# reg-board.net
KiCad netlist of a schematic drawn in EAGLE
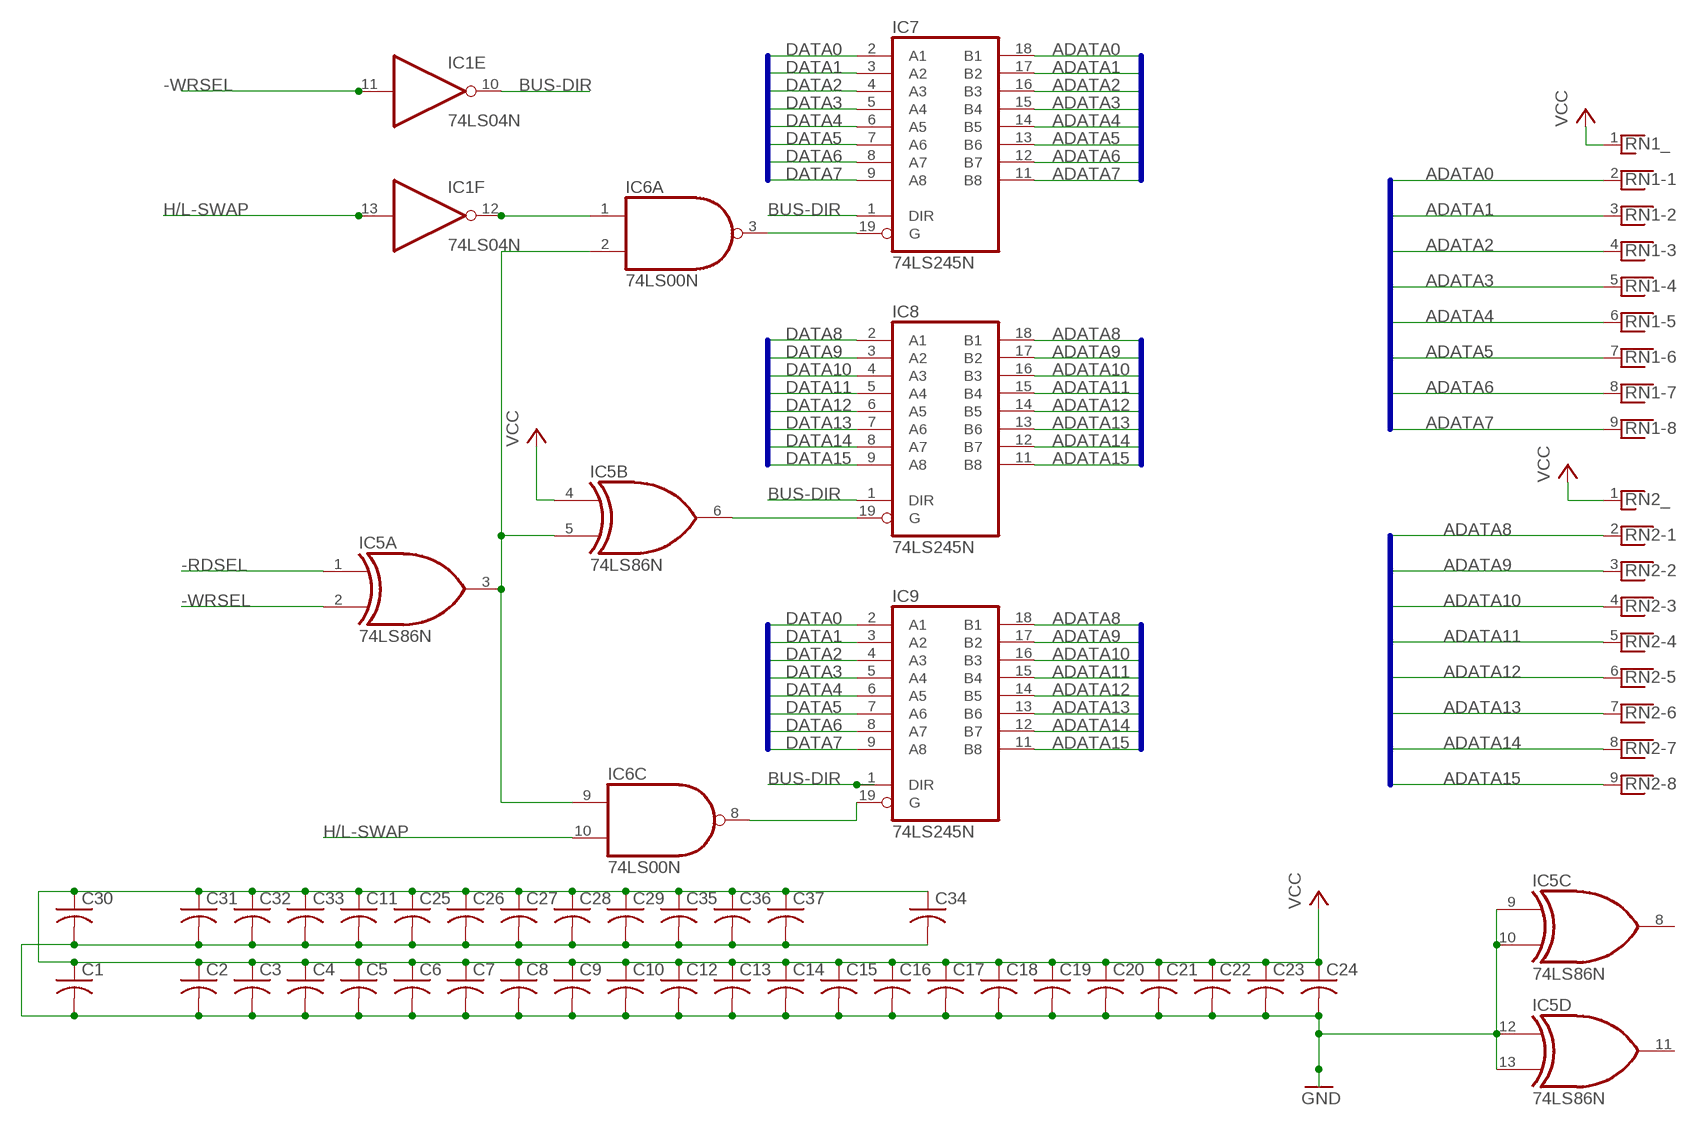
[diagram p0: schematic, sheet 1]
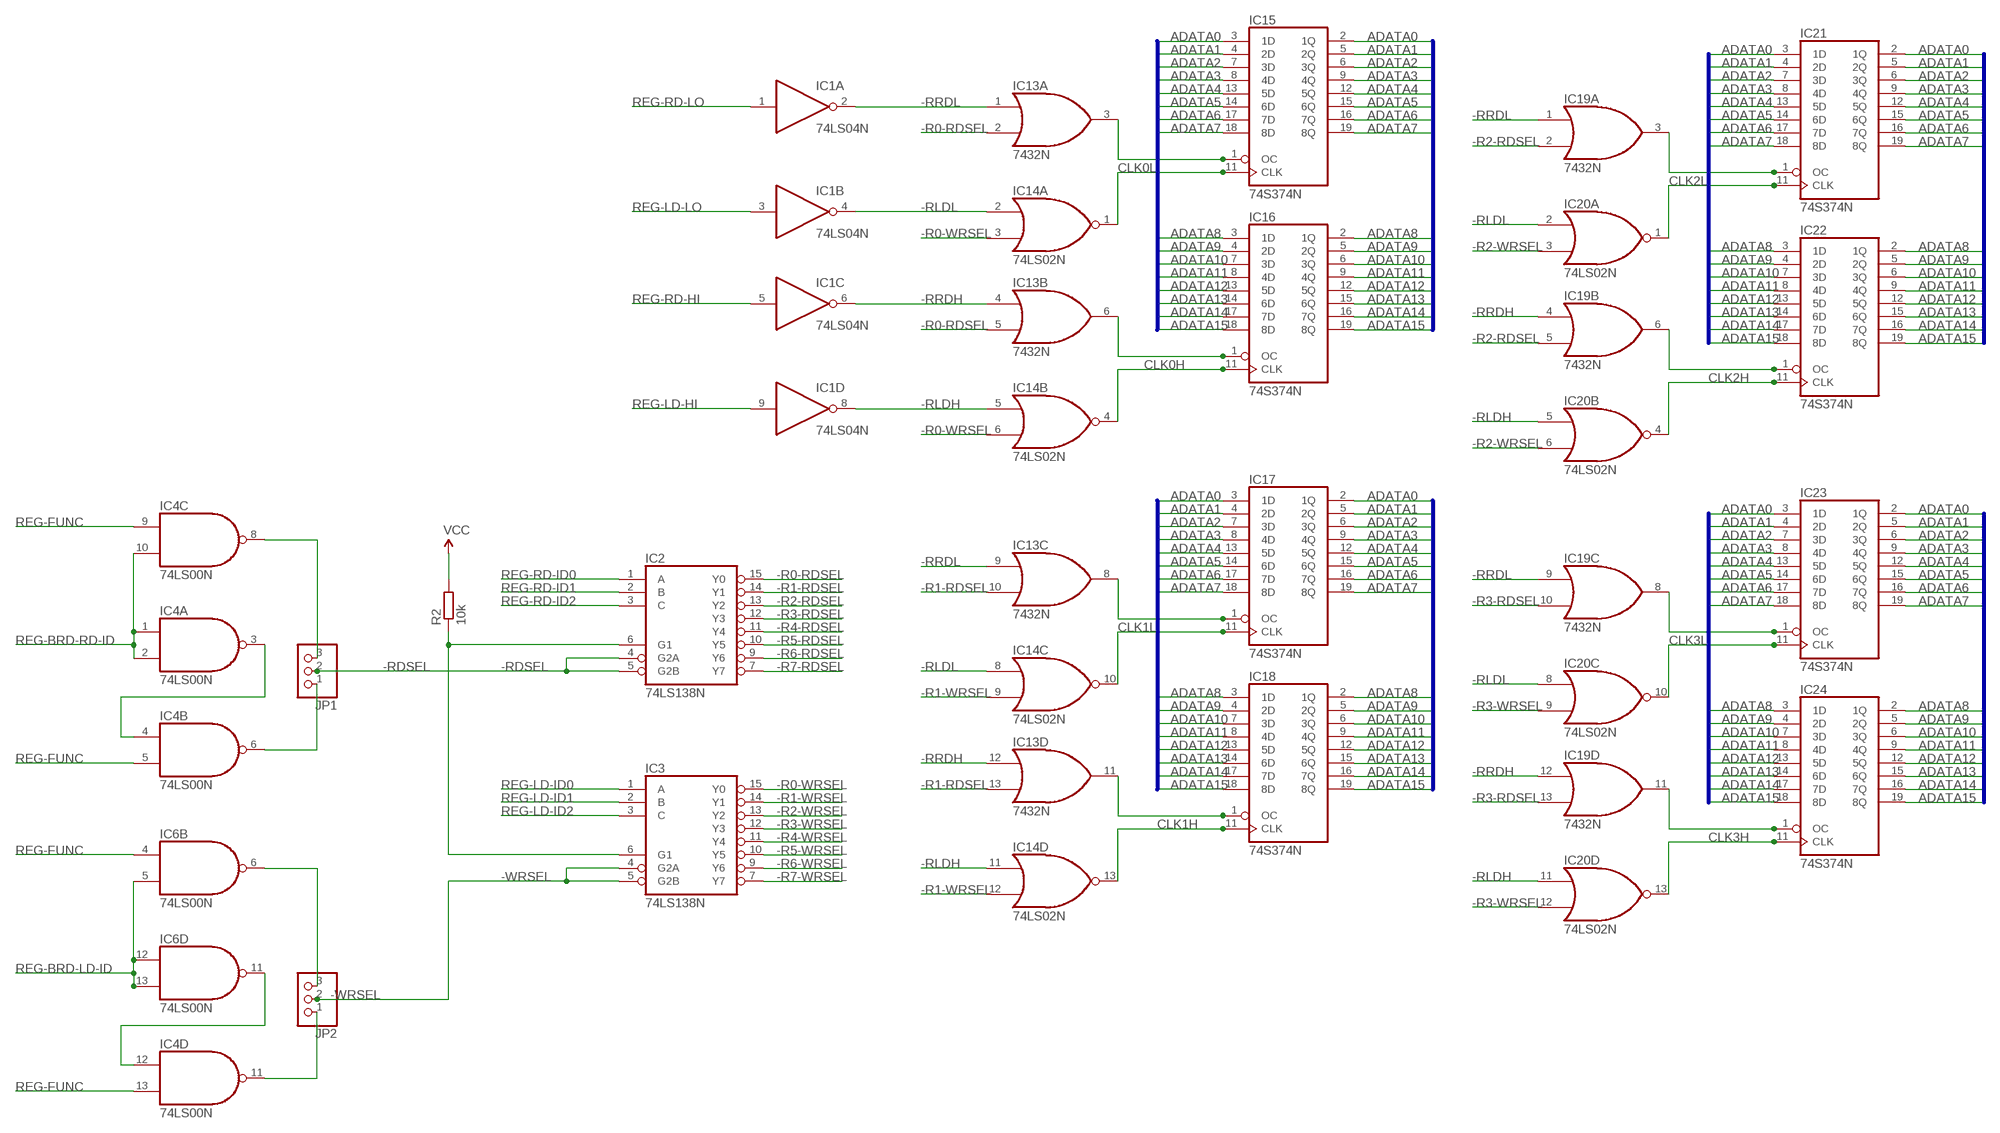
[diagram p1: schematic, sheet 2]
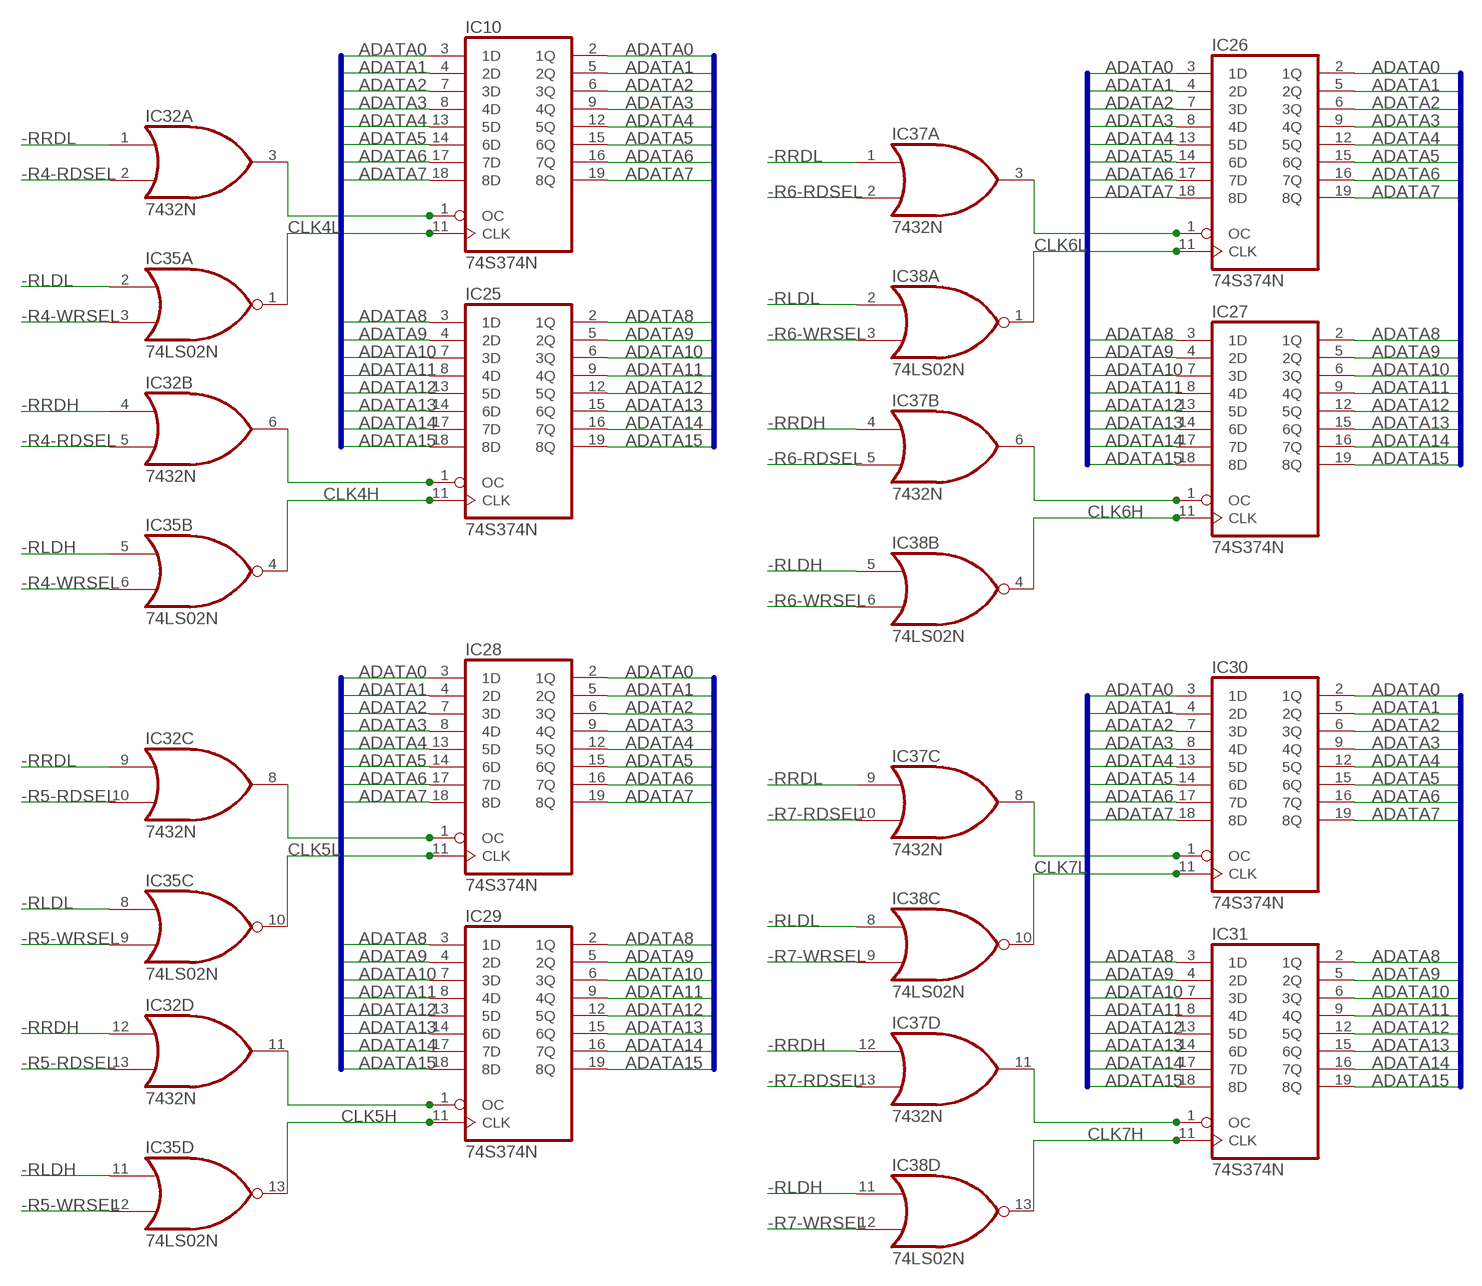
[diagram p2: schematic, sheet 3]
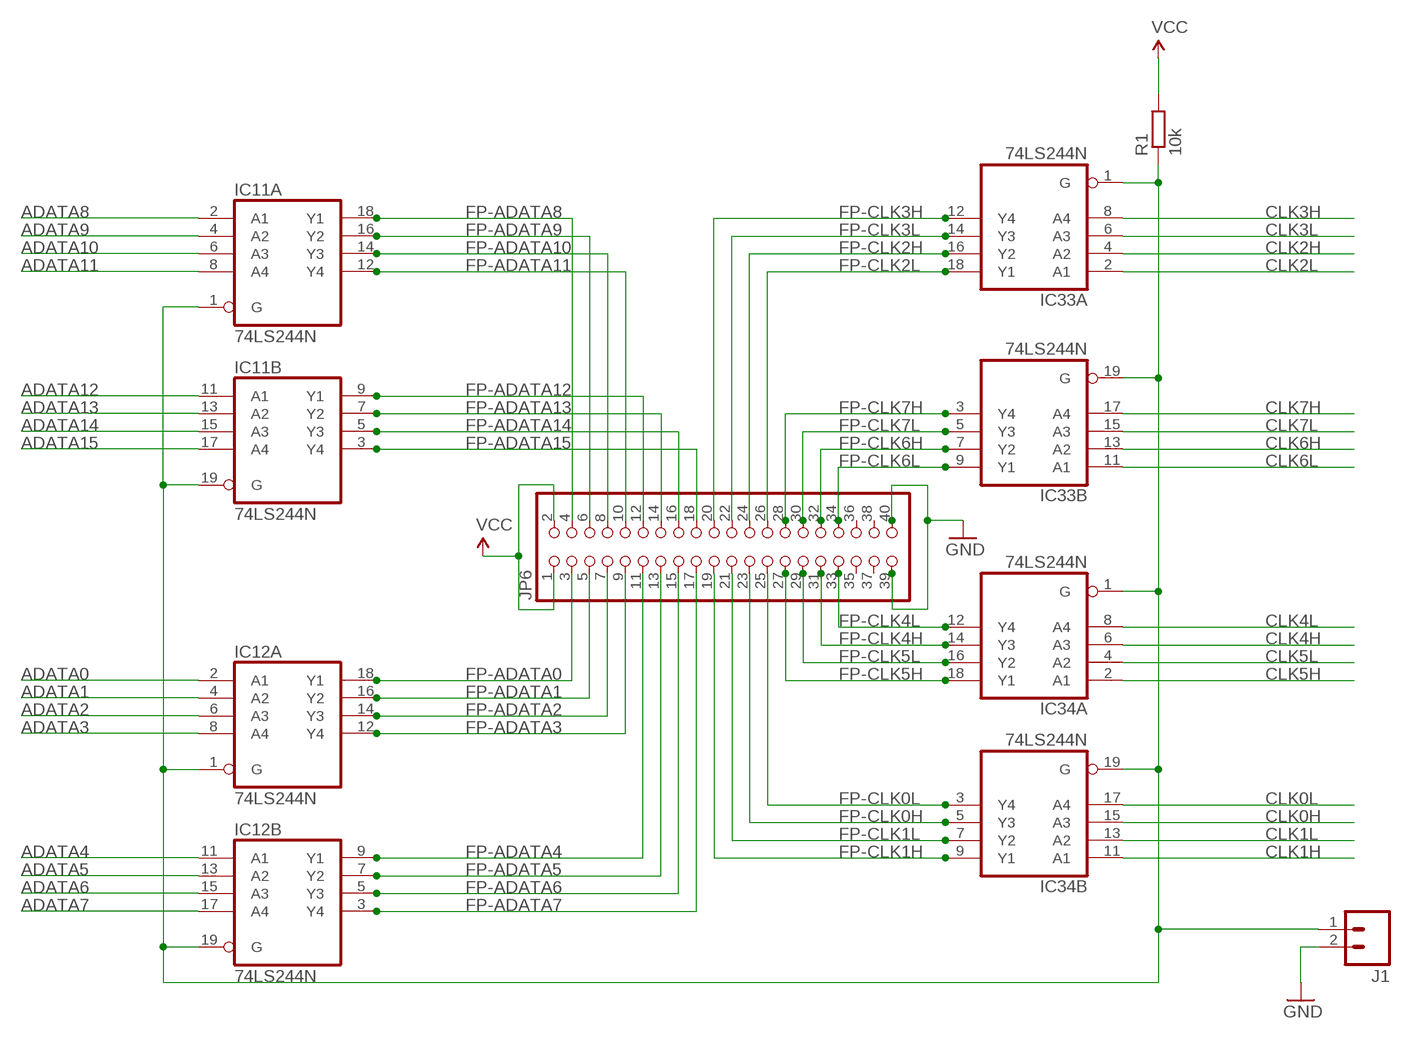
[diagram p3: schematic, sheet 4]
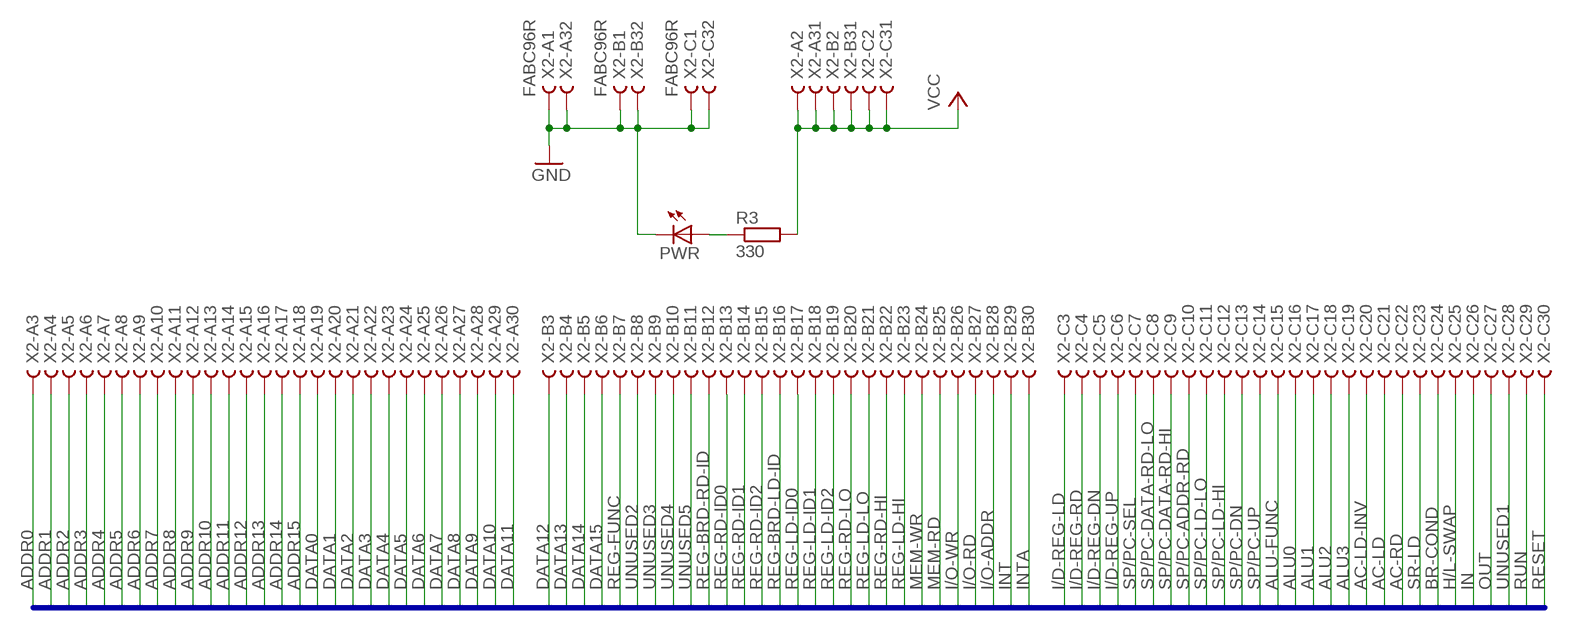
[diagram p4: schematic, sheet 5]

(export (version "E")
  (design (tool "Eeschema 10.0.6"))
  (components
    (comp (ref "IC10")
      (value "74S374N")
      (footprint "eagle-import:DIL20")
      (libsource (lib "eagle-import") (part "74374NS"))
    )
    (comp (ref "IC25")
      (value "74S374N")
      (footprint "eagle-import:DIL20")
      (libsource (lib "eagle-import") (part "74374NS"))
    )
    (comp (ref "IC26")
      (value "74S374N")
      (footprint "eagle-import:DIL20")
      (libsource (lib "eagle-import") (part "74374NS"))
    )
    (comp (ref "IC27")
      (value "74S374N")
      (footprint "eagle-import:DIL20")
      (libsource (lib "eagle-import") (part "74374NS"))
    )
    (comp (ref "IC28")
      (value "74S374N")
      (footprint "eagle-import:DIL20")
      (libsource (lib "eagle-import") (part "74374NS"))
    )
    (comp (ref "IC29")
      (value "74S374N")
      (footprint "eagle-import:DIL20")
      (libsource (lib "eagle-import") (part "74374NS"))
    )
    (comp (ref "IC30")
      (value "74S374N")
      (footprint "eagle-import:DIL20")
      (libsource (lib "eagle-import") (part "74374NS"))
    )
    (comp (ref "IC31")
      (value "74S374N")
      (footprint "eagle-import:DIL20")
      (libsource (lib "eagle-import") (part "74374NS"))
    )
    (comp (ref "IC32")
      (value "7432N")
      (footprint "eagle-import:DIL14")
      (libsource (lib "eagle-import") (part "7432N"))
    )
    (comp (ref "IC35")
      (value "74LS02N")
      (footprint "eagle-import:DIL14")
      (libsource (lib "eagle-import") (part "7402NLS"))
    )
    (comp (ref "IC37")
      (value "7432N")
      (footprint "eagle-import:DIL14")
      (libsource (lib "eagle-import") (part "7432N"))
    )
    (comp (ref "IC38")
      (value "74LS02N")
      (footprint "eagle-import:DIL14")
      (libsource (lib "eagle-import") (part "7402NLS"))
    )
    (comp (ref "IC11")
      (value "74LS244N")
      (footprint "eagle-import:DIL20")
      (libsource (lib "eagle-import") (part "74xx-us_74244NLS"))
    )
    (comp (ref "IC12")
      (value "74LS244N")
      (footprint "eagle-import:DIL20")
      (libsource (lib "eagle-import") (part "74xx-us_74244NLS"))
    )
    (comp (ref "IC33")
      (value "74LS244N")
      (footprint "eagle-import:DIL20")
      (libsource (lib "eagle-import") (part "74xx-us_74244NLS"))
    )
    (comp (ref "IC34")
      (value "74LS244N")
      (footprint "eagle-import:DIL20")
      (libsource (lib "eagle-import") (part "74xx-us_74244NLS"))
    )
    (comp (ref "J1")
      (value "M02PTH")
      (footprint "eagle-import:1X02")
      (libsource (lib "eagle-import") (part "M02PTH"))
    )
    (comp (ref "JP6")
      (value "PINHD-2X20")
      (footprint "eagle-import:2X20")
      (libsource (lib "eagle-import") (part "PINHD-2X20"))
    )
    (comp (ref "R1")
      (value "10k")
      (footprint "eagle-import:0207_10")
      (libsource (lib "eagle-import") (part "R0207/10"))
    )
    (comp (ref "IC1")
      (value "74LS04N")
      (footprint "eagle-import:DIL14")
      (libsource (lib "eagle-import") (part "7404NLS"))
    )
    (comp (ref "IC2")
      (value "74LS138N")
      (footprint "eagle-import:DIL16")
      (libsource (lib "eagle-import") (part "74138NLS"))
    )
    (comp (ref "IC3")
      (value "74LS138N")
      (footprint "eagle-import:DIL16")
      (libsource (lib "eagle-import") (part "74138NLS"))
    )
    (comp (ref "IC4")
      (value "74LS00N")
      (footprint "eagle-import:DIL14")
      (libsource (lib "eagle-import") (part "7400NLS"))
    )
    (comp (ref "IC6")
      (value "74LS00N")
      (footprint "eagle-import:DIL14")
      (libsource (lib "eagle-import") (part "7400NLS"))
    )
    (comp (ref "IC13")
      (value "7432N")
      (footprint "eagle-import:DIL14")
      (libsource (lib "eagle-import") (part "7432N"))
    )
    (comp (ref "IC14")
      (value "74LS02N")
      (footprint "eagle-import:DIL14")
      (libsource (lib "eagle-import") (part "7402NLS"))
    )
    (comp (ref "IC15")
      (value "74S374N")
      (footprint "eagle-import:DIL20")
      (libsource (lib "eagle-import") (part "74374NS"))
    )
    (comp (ref "IC16")
      (value "74S374N")
      (footprint "eagle-import:DIL20")
      (libsource (lib "eagle-import") (part "74374NS"))
    )
    (comp (ref "IC17")
      (value "74S374N")
      (footprint "eagle-import:DIL20")
      (libsource (lib "eagle-import") (part "74374NS"))
    )
    (comp (ref "IC18")
      (value "74S374N")
      (footprint "eagle-import:DIL20")
      (libsource (lib "eagle-import") (part "74374NS"))
    )
    (comp (ref "IC19")
      (value "7432N")
      (footprint "eagle-import:DIL14")
      (libsource (lib "eagle-import") (part "7432N"))
    )
    (comp (ref "IC20")
      (value "74LS02N")
      (footprint "eagle-import:DIL14")
      (libsource (lib "eagle-import") (part "7402NLS"))
    )
    (comp (ref "IC21")
      (value "74S374N")
      (footprint "eagle-import:DIL20")
      (libsource (lib "eagle-import") (part "74374NS"))
    )
    (comp (ref "IC22")
      (value "74S374N")
      (footprint "eagle-import:DIL20")
      (libsource (lib "eagle-import") (part "74374NS"))
    )
    (comp (ref "IC23")
      (value "74S374N")
      (footprint "eagle-import:DIL20")
      (libsource (lib "eagle-import") (part "74374NS"))
    )
    (comp (ref "IC24")
      (value "74S374N")
      (footprint "eagle-import:DIL20")
      (libsource (lib "eagle-import") (part "74374NS"))
    )
    (comp (ref "JP1")
      (value "PINHD-1X3")
      (footprint "eagle-import:1X03")
      (libsource (lib "eagle-import") (part "PINHD-1X3"))
    )
    (comp (ref "JP2")
      (value "PINHD-1X3")
      (footprint "eagle-import:1X03")
      (libsource (lib "eagle-import") (part "PINHD-1X3"))
    )
    (comp (ref "R2")
      (value "10k")
      (footprint "eagle-import:0207_10")
      (libsource (lib "eagle-import") (part "R0207/10"))
    )
    (comp (ref "C1")
      (value "C-US025-040X050")
      (footprint "eagle-import:C025-040X050")
      (libsource (lib "eagle-import") (part "C-US025-040X050"))
    )
    (comp (ref "C2")
      (value "C-US025-040X050")
      (footprint "eagle-import:C025-040X050")
      (libsource (lib "eagle-import") (part "C-US025-040X050"))
    )
    (comp (ref "C3")
      (value "C-US025-040X050")
      (footprint "eagle-import:C025-040X050")
      (libsource (lib "eagle-import") (part "C-US025-040X050"))
    )
    (comp (ref "C4")
      (value "C-US025-040X050")
      (footprint "eagle-import:C025-040X050")
      (libsource (lib "eagle-import") (part "C-US025-040X050"))
    )
    (comp (ref "C5")
      (value "C-US025-040X050")
      (footprint "eagle-import:C025-040X050")
      (libsource (lib "eagle-import") (part "C-US025-040X050"))
    )
    (comp (ref "C6")
      (value "C-US025-040X050")
      (footprint "eagle-import:C025-040X050")
      (libsource (lib "eagle-import") (part "C-US025-040X050"))
    )
    (comp (ref "C7")
      (value "C-US025-040X050")
      (footprint "eagle-import:C025-040X050")
      (libsource (lib "eagle-import") (part "C-US025-040X050"))
    )
    (comp (ref "C8")
      (value "C-US025-040X050")
      (footprint "eagle-import:C025-040X050")
      (libsource (lib "eagle-import") (part "C-US025-040X050"))
    )
    (comp (ref "C9")
      (value "C-US025-040X050")
      (footprint "eagle-import:C025-040X050")
      (libsource (lib "eagle-import") (part "C-US025-040X050"))
    )
    (comp (ref "C10")
      (value "C-US025-040X050")
      (footprint "eagle-import:C025-040X050")
      (libsource (lib "eagle-import") (part "C-US025-040X050"))
    )
    (comp (ref "C11")
      (value "C-US025-040X050")
      (footprint "eagle-import:C025-040X050")
      (libsource (lib "eagle-import") (part "C-US025-040X050"))
    )
    (comp (ref "C12")
      (value "C-US025-040X050")
      (footprint "eagle-import:C025-040X050")
      (libsource (lib "eagle-import") (part "C-US025-040X050"))
    )
    (comp (ref "C13")
      (value "C-US025-040X050")
      (footprint "eagle-import:C025-040X050")
      (libsource (lib "eagle-import") (part "C-US025-040X050"))
    )
    (comp (ref "C14")
      (value "C-US025-040X050")
      (footprint "eagle-import:C025-040X050")
      (libsource (lib "eagle-import") (part "C-US025-040X050"))
    )
    (comp (ref "C15")
      (value "C-US025-040X050")
      (footprint "eagle-import:C025-040X050")
      (libsource (lib "eagle-import") (part "C-US025-040X050"))
    )
    (comp (ref "C16")
      (value "C-US025-040X050")
      (footprint "eagle-import:C025-040X050")
      (libsource (lib "eagle-import") (part "C-US025-040X050"))
    )
    (comp (ref "C17")
      (value "C-US025-040X050")
      (footprint "eagle-import:C025-040X050")
      (libsource (lib "eagle-import") (part "C-US025-040X050"))
    )
    (comp (ref "C18")
      (value "C-US025-040X050")
      (footprint "eagle-import:C025-040X050")
      (libsource (lib "eagle-import") (part "C-US025-040X050"))
    )
    (comp (ref "C19")
      (value "C-US025-040X050")
      (footprint "eagle-import:C025-040X050")
      (libsource (lib "eagle-import") (part "C-US025-040X050"))
    )
    (comp (ref "C20")
      (value "C-US025-040X050")
      (footprint "eagle-import:C025-040X050")
      (libsource (lib "eagle-import") (part "C-US025-040X050"))
    )
    (comp (ref "C21")
      (value "C-US025-040X050")
      (footprint "eagle-import:C025-040X050")
      (libsource (lib "eagle-import") (part "C-US025-040X050"))
    )
    (comp (ref "C22")
      (value "C-US025-040X050")
      (footprint "eagle-import:C025-040X050")
      (libsource (lib "eagle-import") (part "C-US025-040X050"))
    )
    (comp (ref "C23")
      (value "C-US025-040X050")
      (footprint "eagle-import:C025-040X050")
      (libsource (lib "eagle-import") (part "C-US025-040X050"))
    )
    (comp (ref "C24")
      (value "C-US025-040X050")
      (footprint "eagle-import:C025-040X050")
      (libsource (lib "eagle-import") (part "C-US025-040X050"))
    )
    (comp (ref "C25")
      (value "C-US025-040X050")
      (footprint "eagle-import:C025-040X050")
      (libsource (lib "eagle-import") (part "C-US025-040X050"))
    )
    (comp (ref "C26")
      (value "C-US025-040X050")
      (footprint "eagle-import:C025-040X050")
      (libsource (lib "eagle-import") (part "C-US025-040X050"))
    )
    (comp (ref "C27")
      (value "C-US025-040X050")
      (footprint "eagle-import:C025-040X050")
      (libsource (lib "eagle-import") (part "C-US025-040X050"))
    )
    (comp (ref "C28")
      (value "C-US025-040X050")
      (footprint "eagle-import:C025-040X050")
      (libsource (lib "eagle-import") (part "C-US025-040X050"))
    )
    (comp (ref "C29")
      (value "C-US025-040X050")
      (footprint "eagle-import:C025-040X050")
      (libsource (lib "eagle-import") (part "C-US025-040X050"))
    )
    (comp (ref "C30")
      (value "C-US025-040X050")
      (footprint "eagle-import:C025-040X050")
      (libsource (lib "eagle-import") (part "C-US025-040X050"))
    )
    (comp (ref "C31")
      (value "C-US025-040X050")
      (footprint "eagle-import:C025-040X050")
      (libsource (lib "eagle-import") (part "C-US025-040X050"))
    )
    (comp (ref "C32")
      (value "C-US025-040X050")
      (footprint "eagle-import:C025-040X050")
      (libsource (lib "eagle-import") (part "C-US025-040X050"))
    )
    (comp (ref "C33")
      (value "C-US025-040X050")
      (footprint "eagle-import:C025-040X050")
      (libsource (lib "eagle-import") (part "C-US025-040X050"))
    )
    (comp (ref "C34")
      (value "C-US025-040X050")
      (footprint "eagle-import:C025-040X050")
      (libsource (lib "eagle-import") (part "C-US025-040X050"))
    )
    (comp (ref "C35")
      (value "C-US025-040X050")
      (footprint "eagle-import:C025-040X050")
      (libsource (lib "eagle-import") (part "C-US025-040X050"))
    )
    (comp (ref "C36")
      (value "C-US025-040X050")
      (footprint "eagle-import:C025-040X050")
      (libsource (lib "eagle-import") (part "C-US025-040X050"))
    )
    (comp (ref "C37")
      (value "C-US025-040X050")
      (footprint "eagle-import:C025-040X050")
      (libsource (lib "eagle-import") (part "C-US025-040X050"))
    )
    (comp (ref "IC5")
      (value "74LS86N")
      (footprint "eagle-import:DIL14")
      (libsource (lib "eagle-import") (part "7486NLS"))
    )
    (comp (ref "IC7")
      (value "74LS245N")
      (footprint "eagle-import:DIL20")
      (libsource (lib "eagle-import") (part "74245NLS"))
    )
    (comp (ref "IC8")
      (value "74LS245N")
      (footprint "eagle-import:DIL20")
      (libsource (lib "eagle-import") (part "74245NLS"))
    )
    (comp (ref "IC9")
      (value "74LS245N")
      (footprint "eagle-import:DIL20")
      (libsource (lib "eagle-import") (part "74245NLS"))
    )
    (comp (ref "RN1")
      (value "RNX8")
      (footprint "eagle-import:RN-9")
      (libsource (lib "eagle-import") (part "RNX8"))
    )
    (comp (ref "RN2")
      (value "RNX8")
      (footprint "eagle-import:RN-9")
      (libsource (lib "eagle-import") (part "RNX8"))
    )
    (comp (ref "PWR")
      (value "LED5MM")
      (footprint "eagle-import:LED5MM")
      (libsource (lib "eagle-import") (part "LED5MM"))
    )
    (comp (ref "R3")
      (value "330")
      (footprint "eagle-import:0207_10")
      (libsource (lib "eagle-import") (part "R0207/10"))
    )
    (comp (ref "X2")
      (value "FABC96R")
      (footprint "eagle-import:FABC96R")
      (libsource (lib "eagle-import") (part "FABC96R"))
    )
  )
  (nets
    (net (code "1") (name "-R0-RDSEL") (class "Default")
      (node (ref "IC13") (pin "2") (pinfunction "I1_2") (pintype "input"))
      (node (ref "IC13") (pin "5") (pinfunction "I1_5") (pintype "input"))
      (node (ref "IC2") (pin "15") (pinfunction "Y0_15") (pintype "output"))
    )
    (net (code "2") (name "-R0-WRSEL") (class "Default")
      (node (ref "IC14") (pin "3") (pinfunction "I1_3") (pintype "input"))
      (node (ref "IC14") (pin "6") (pinfunction "I1_6") (pintype "input"))
      (node (ref "IC3") (pin "15") (pinfunction "Y0_15") (pintype "output"))
    )
    (net (code "3") (name "-R1-RDSEL") (class "Default")
      (node (ref "IC13") (pin "10") (pinfunction "I1_10") (pintype "input"))
      (node (ref "IC13") (pin "13") (pinfunction "I1_13") (pintype "input"))
      (node (ref "IC2") (pin "14") (pinfunction "Y1_14") (pintype "output"))
    )
    (net (code "4") (name "-R1-WRSEL") (class "Default")
      (node (ref "IC14") (pin "12") (pinfunction "I1_12") (pintype "input"))
      (node (ref "IC14") (pin "9") (pinfunction "I1_9") (pintype "input"))
      (node (ref "IC3") (pin "14") (pinfunction "Y1_14") (pintype "output"))
    )
    (net (code "5") (name "-R2-RDSEL") (class "Default")
      (node (ref "IC19") (pin "2") (pinfunction "I1_2") (pintype "input"))
      (node (ref "IC19") (pin "5") (pinfunction "I1_5") (pintype "input"))
      (node (ref "IC2") (pin "13") (pinfunction "Y2_13") (pintype "output"))
    )
    (net (code "6") (name "-R2-WRSEL") (class "Default")
      (node (ref "IC20") (pin "3") (pinfunction "I1_3") (pintype "input"))
      (node (ref "IC20") (pin "6") (pinfunction "I1_6") (pintype "input"))
      (node (ref "IC3") (pin "13") (pinfunction "Y2_13") (pintype "output"))
    )
    (net (code "7") (name "-R3-RDSEL") (class "Default")
      (node (ref "IC19") (pin "10") (pinfunction "I1_10") (pintype "input"))
      (node (ref "IC19") (pin "13") (pinfunction "I1_13") (pintype "input"))
      (node (ref "IC2") (pin "12") (pinfunction "Y3_12") (pintype "output"))
    )
    (net (code "8") (name "-R3-WRSEL") (class "Default")
      (node (ref "IC20") (pin "12") (pinfunction "I1_12") (pintype "input"))
      (node (ref "IC20") (pin "9") (pinfunction "I1_9") (pintype "input"))
      (node (ref "IC3") (pin "12") (pinfunction "Y3_12") (pintype "output"))
    )
    (net (code "9") (name "-R4-RDSEL") (class "Default")
      (node (ref "IC2") (pin "11") (pinfunction "Y4_11") (pintype "output"))
      (node (ref "IC32") (pin "2") (pinfunction "I1_2") (pintype "input"))
      (node (ref "IC32") (pin "5") (pinfunction "I1_5") (pintype "input"))
    )
    (net (code "10") (name "-R4-WRSEL") (class "Default")
      (node (ref "IC3") (pin "11") (pinfunction "Y4_11") (pintype "output"))
      (node (ref "IC35") (pin "3") (pinfunction "I1_3") (pintype "input"))
      (node (ref "IC35") (pin "6") (pinfunction "I1_6") (pintype "input"))
    )
    (net (code "11") (name "-R5-RDSEL") (class "Default")
      (node (ref "IC2") (pin "10") (pinfunction "Y5_10") (pintype "output"))
      (node (ref "IC32") (pin "10") (pinfunction "I1_10") (pintype "input"))
      (node (ref "IC32") (pin "13") (pinfunction "I1_13") (pintype "input"))
    )
    (net (code "12") (name "-R5-WRSEL") (class "Default")
      (node (ref "IC3") (pin "10") (pinfunction "Y5_10") (pintype "output"))
      (node (ref "IC35") (pin "12") (pinfunction "I1_12") (pintype "input"))
      (node (ref "IC35") (pin "9") (pinfunction "I1_9") (pintype "input"))
    )
    (net (code "13") (name "-R6-RDSEL") (class "Default")
      (node (ref "IC2") (pin "9") (pinfunction "Y6_9") (pintype "output"))
      (node (ref "IC37") (pin "2") (pinfunction "I1_2") (pintype "input"))
      (node (ref "IC37") (pin "5") (pinfunction "I1_5") (pintype "input"))
    )
    (net (code "14") (name "-R6-WRSEL") (class "Default")
      (node (ref "IC3") (pin "9") (pinfunction "Y6_9") (pintype "output"))
      (node (ref "IC38") (pin "3") (pinfunction "I1_3") (pintype "input"))
      (node (ref "IC38") (pin "6") (pinfunction "I1_6") (pintype "input"))
    )
    (net (code "15") (name "-R7-RDSEL") (class "Default")
      (node (ref "IC2") (pin "7") (pinfunction "Y7_7") (pintype "output"))
      (node (ref "IC37") (pin "10") (pinfunction "I1_10") (pintype "input"))
      (node (ref "IC37") (pin "13") (pinfunction "I1_13") (pintype "input"))
    )
    (net (code "16") (name "-R7-WRSEL") (class "Default")
      (node (ref "IC3") (pin "7") (pinfunction "Y7_7") (pintype "output"))
      (node (ref "IC38") (pin "12") (pinfunction "I1_12") (pintype "input"))
      (node (ref "IC38") (pin "9") (pinfunction "I1_9") (pintype "input"))
    )
    (net (code "17") (name "-RDSEL") (class "Default")
      (node (ref "IC2") (pin "4") (pinfunction "G2A_4") (pintype "input"))
      (node (ref "IC2") (pin "5") (pinfunction "G2B_5") (pintype "input"))
      (node (ref "IC5") (pin "1") (pinfunction "I0_1") (pintype "input"))
      (node (ref "JP1") (pin "2") (pinfunction "2_2") (pintype "passive"))
    )
    (net (code "18") (name "-RLDH") (class "Default")
      (node (ref "IC1") (pin "8") (pinfunction "O_8") (pintype "output"))
      (node (ref "IC14") (pin "11") (pinfunction "I0_11") (pintype "input"))
      (node (ref "IC14") (pin "5") (pinfunction "I0_5") (pintype "input"))
      (node (ref "IC20") (pin "11") (pinfunction "I0_11") (pintype "input"))
      (node (ref "IC20") (pin "5") (pinfunction "I0_5") (pintype "input"))
      (node (ref "IC35") (pin "11") (pinfunction "I0_11") (pintype "input"))
      (node (ref "IC35") (pin "5") (pinfunction "I0_5") (pintype "input"))
      (node (ref "IC38") (pin "11") (pinfunction "I0_11") (pintype "input"))
      (node (ref "IC38") (pin "5") (pinfunction "I0_5") (pintype "input"))
    )
    (net (code "19") (name "-RLDL") (class "Default")
      (node (ref "IC1") (pin "4") (pinfunction "O_4") (pintype "output"))
      (node (ref "IC14") (pin "2") (pinfunction "I0_2") (pintype "input"))
      (node (ref "IC14") (pin "8") (pinfunction "I0_8") (pintype "input"))
      (node (ref "IC20") (pin "2") (pinfunction "I0_2") (pintype "input"))
      (node (ref "IC20") (pin "8") (pinfunction "I0_8") (pintype "input"))
      (node (ref "IC35") (pin "2") (pinfunction "I0_2") (pintype "input"))
      (node (ref "IC35") (pin "8") (pinfunction "I0_8") (pintype "input"))
      (node (ref "IC38") (pin "2") (pinfunction "I0_2") (pintype "input"))
      (node (ref "IC38") (pin "8") (pinfunction "I0_8") (pintype "input"))
    )
    (net (code "20") (name "-RRDH") (class "Default")
      (node (ref "IC1") (pin "6") (pinfunction "O_6") (pintype "output"))
      (node (ref "IC13") (pin "12") (pinfunction "I0_12") (pintype "input"))
      (node (ref "IC13") (pin "4") (pinfunction "I0_4") (pintype "input"))
      (node (ref "IC19") (pin "12") (pinfunction "I0_12") (pintype "input"))
      (node (ref "IC19") (pin "4") (pinfunction "I0_4") (pintype "input"))
      (node (ref "IC32") (pin "12") (pinfunction "I0_12") (pintype "input"))
      (node (ref "IC32") (pin "4") (pinfunction "I0_4") (pintype "input"))
      (node (ref "IC37") (pin "12") (pinfunction "I0_12") (pintype "input"))
      (node (ref "IC37") (pin "4") (pinfunction "I0_4") (pintype "input"))
    )
    (net (code "21") (name "-RRDL") (class "Default")
      (node (ref "IC1") (pin "2") (pinfunction "O_2") (pintype "output"))
      (node (ref "IC13") (pin "1") (pinfunction "I0_1") (pintype "input"))
      (node (ref "IC13") (pin "9") (pinfunction "I0_9") (pintype "input"))
      (node (ref "IC19") (pin "1") (pinfunction "I0_1") (pintype "input"))
      (node (ref "IC19") (pin "9") (pinfunction "I0_9") (pintype "input"))
      (node (ref "IC32") (pin "1") (pinfunction "I0_1") (pintype "input"))
      (node (ref "IC32") (pin "9") (pinfunction "I0_9") (pintype "input"))
      (node (ref "IC37") (pin "1") (pinfunction "I0_1") (pintype "input"))
      (node (ref "IC37") (pin "9") (pinfunction "I0_9") (pintype "input"))
    )
    (net (code "22") (name "-WRSEL") (class "Default")
      (node (ref "IC1") (pin "11") (pinfunction "I_11") (pintype "input"))
      (node (ref "IC3") (pin "4") (pinfunction "G2A_4") (pintype "input"))
      (node (ref "IC3") (pin "5") (pinfunction "G2B_5") (pintype "input"))
      (node (ref "IC5") (pin "2") (pinfunction "I1_2") (pintype "input"))
      (node (ref "JP2") (pin "2") (pinfunction "2_2") (pintype "passive"))
    )
    (net (code "23") (name "AC-LD") (class "Default")
      (node (ref "X2") (pin "C21") (pinfunction "B_C21") (pintype "passive"))
    )
    (net (code "24") (name "AC-LD-INV") (class "Default")
      (node (ref "X2") (pin "C20") (pinfunction "B_C20") (pintype "passive"))
    )
    (net (code "25") (name "AC-RD") (class "Default")
      (node (ref "X2") (pin "C22") (pinfunction "B_C22") (pintype "passive"))
    )
    (net (code "26") (name "ADATA0") (class "Default")
      (node (ref "IC10") (pin "2") (pinfunction "1Q_2") (pintype "tri_state"))
      (node (ref "IC10") (pin "3") (pinfunction "1D_3") (pintype "input"))
      (node (ref "IC12") (pin "2") (pinfunction "A1_2") (pintype "input"))
      (node (ref "IC15") (pin "2") (pinfunction "1Q_2") (pintype "tri_state"))
      (node (ref "IC15") (pin "3") (pinfunction "1D_3") (pintype "input"))
      (node (ref "IC17") (pin "2") (pinfunction "1Q_2") (pintype "tri_state"))
      (node (ref "IC17") (pin "3") (pinfunction "1D_3") (pintype "input"))
      (node (ref "IC21") (pin "2") (pinfunction "1Q_2") (pintype "tri_state"))
      (node (ref "IC21") (pin "3") (pinfunction "1D_3") (pintype "input"))
      (node (ref "IC23") (pin "2") (pinfunction "1Q_2") (pintype "tri_state"))
      (node (ref "IC23") (pin "3") (pinfunction "1D_3") (pintype "input"))
      (node (ref "IC26") (pin "2") (pinfunction "1Q_2") (pintype "tri_state"))
      (node (ref "IC26") (pin "3") (pinfunction "1D_3") (pintype "input"))
      (node (ref "IC28") (pin "2") (pinfunction "1Q_2") (pintype "tri_state"))
      (node (ref "IC28") (pin "3") (pinfunction "1D_3") (pintype "input"))
      (node (ref "IC30") (pin "2") (pinfunction "1Q_2") (pintype "tri_state"))
      (node (ref "IC30") (pin "3") (pinfunction "1D_3") (pintype "input"))
      (node (ref "IC7") (pin "18") (pinfunction "B1_18") (pintype "bidirectional"))
      (node (ref "RN1") (pin "2") (pinfunction "1_2") (pintype "passive"))
    )
    (net (code "27") (name "ADATA1") (class "Default")
      (node (ref "IC10") (pin "4") (pinfunction "2D_4") (pintype "input"))
      (node (ref "IC10") (pin "5") (pinfunction "2Q_5") (pintype "tri_state"))
      (node (ref "IC12") (pin "4") (pinfunction "A2_4") (pintype "input"))
      (node (ref "IC15") (pin "4") (pinfunction "2D_4") (pintype "input"))
      (node (ref "IC15") (pin "5") (pinfunction "2Q_5") (pintype "tri_state"))
      (node (ref "IC17") (pin "4") (pinfunction "2D_4") (pintype "input"))
      (node (ref "IC17") (pin "5") (pinfunction "2Q_5") (pintype "tri_state"))
      (node (ref "IC21") (pin "4") (pinfunction "2D_4") (pintype "input"))
      (node (ref "IC21") (pin "5") (pinfunction "2Q_5") (pintype "tri_state"))
      (node (ref "IC23") (pin "4") (pinfunction "2D_4") (pintype "input"))
      (node (ref "IC23") (pin "5") (pinfunction "2Q_5") (pintype "tri_state"))
      (node (ref "IC26") (pin "4") (pinfunction "2D_4") (pintype "input"))
      (node (ref "IC26") (pin "5") (pinfunction "2Q_5") (pintype "tri_state"))
      (node (ref "IC28") (pin "4") (pinfunction "2D_4") (pintype "input"))
      (node (ref "IC28") (pin "5") (pinfunction "2Q_5") (pintype "tri_state"))
      (node (ref "IC30") (pin "4") (pinfunction "2D_4") (pintype "input"))
      (node (ref "IC30") (pin "5") (pinfunction "2Q_5") (pintype "tri_state"))
      (node (ref "IC7") (pin "17") (pinfunction "B2_17") (pintype "bidirectional"))
      (node (ref "RN1") (pin "3") (pinfunction "1_3") (pintype "passive"))
    )
    (net (code "28") (name "ADATA2") (class "Default")
      (node (ref "IC10") (pin "6") (pinfunction "3Q_6") (pintype "tri_state"))
      (node (ref "IC10") (pin "7") (pinfunction "3D_7") (pintype "input"))
      (node (ref "IC12") (pin "6") (pinfunction "A3_6") (pintype "input"))
      (node (ref "IC15") (pin "6") (pinfunction "3Q_6") (pintype "tri_state"))
      (node (ref "IC15") (pin "7") (pinfunction "3D_7") (pintype "input"))
      (node (ref "IC17") (pin "6") (pinfunction "3Q_6") (pintype "tri_state"))
      (node (ref "IC17") (pin "7") (pinfunction "3D_7") (pintype "input"))
      (node (ref "IC21") (pin "6") (pinfunction "3Q_6") (pintype "tri_state"))
      (node (ref "IC21") (pin "7") (pinfunction "3D_7") (pintype "input"))
      (node (ref "IC23") (pin "6") (pinfunction "3Q_6") (pintype "tri_state"))
      (node (ref "IC23") (pin "7") (pinfunction "3D_7") (pintype "input"))
      (node (ref "IC26") (pin "6") (pinfunction "3Q_6") (pintype "tri_state"))
      (node (ref "IC26") (pin "7") (pinfunction "3D_7") (pintype "input"))
      (node (ref "IC28") (pin "6") (pinfunction "3Q_6") (pintype "tri_state"))
      (node (ref "IC28") (pin "7") (pinfunction "3D_7") (pintype "input"))
      (node (ref "IC30") (pin "6") (pinfunction "3Q_6") (pintype "tri_state"))
      (node (ref "IC30") (pin "7") (pinfunction "3D_7") (pintype "input"))
      (node (ref "IC7") (pin "16") (pinfunction "B3_16") (pintype "bidirectional"))
      (node (ref "RN1") (pin "4") (pinfunction "1_4") (pintype "passive"))
    )
    (net (code "29") (name "ADATA3") (class "Default")
      (node (ref "IC10") (pin "8") (pinfunction "4D_8") (pintype "input"))
      (node (ref "IC10") (pin "9") (pinfunction "4Q_9") (pintype "tri_state"))
      (node (ref "IC12") (pin "8") (pinfunction "A4_8") (pintype "input"))
      (node (ref "IC15") (pin "8") (pinfunction "4D_8") (pintype "input"))
      (node (ref "IC15") (pin "9") (pinfunction "4Q_9") (pintype "tri_state"))
      (node (ref "IC17") (pin "8") (pinfunction "4D_8") (pintype "input"))
      (node (ref "IC17") (pin "9") (pinfunction "4Q_9") (pintype "tri_state"))
      (node (ref "IC21") (pin "8") (pinfunction "4D_8") (pintype "input"))
      (node (ref "IC21") (pin "9") (pinfunction "4Q_9") (pintype "tri_state"))
      (node (ref "IC23") (pin "8") (pinfunction "4D_8") (pintype "input"))
      (node (ref "IC23") (pin "9") (pinfunction "4Q_9") (pintype "tri_state"))
      (node (ref "IC26") (pin "8") (pinfunction "4D_8") (pintype "input"))
      (node (ref "IC26") (pin "9") (pinfunction "4Q_9") (pintype "tri_state"))
      (node (ref "IC28") (pin "8") (pinfunction "4D_8") (pintype "input"))
      (node (ref "IC28") (pin "9") (pinfunction "4Q_9") (pintype "tri_state"))
      (node (ref "IC30") (pin "8") (pinfunction "4D_8") (pintype "input"))
      (node (ref "IC30") (pin "9") (pinfunction "4Q_9") (pintype "tri_state"))
      (node (ref "IC7") (pin "15") (pinfunction "B4_15") (pintype "bidirectional"))
      (node (ref "RN1") (pin "5") (pinfunction "1_5") (pintype "passive"))
    )
    (net (code "30") (name "ADATA4") (class "Default")
      (node (ref "IC10") (pin "12") (pinfunction "5Q_12") (pintype "tri_state"))
      (node (ref "IC10") (pin "13") (pinfunction "5D_13") (pintype "input"))
      (node (ref "IC12") (pin "11") (pinfunction "A1_11") (pintype "input"))
      (node (ref "IC15") (pin "12") (pinfunction "5Q_12") (pintype "tri_state"))
      (node (ref "IC15") (pin "13") (pinfunction "5D_13") (pintype "input"))
      (node (ref "IC17") (pin "12") (pinfunction "5Q_12") (pintype "tri_state"))
      (node (ref "IC17") (pin "13") (pinfunction "5D_13") (pintype "input"))
      (node (ref "IC21") (pin "12") (pinfunction "5Q_12") (pintype "tri_state"))
      (node (ref "IC21") (pin "13") (pinfunction "5D_13") (pintype "input"))
      (node (ref "IC23") (pin "12") (pinfunction "5Q_12") (pintype "tri_state"))
      (node (ref "IC23") (pin "13") (pinfunction "5D_13") (pintype "input"))
      (node (ref "IC26") (pin "12") (pinfunction "5Q_12") (pintype "tri_state"))
      (node (ref "IC26") (pin "13") (pinfunction "5D_13") (pintype "input"))
      (node (ref "IC28") (pin "12") (pinfunction "5Q_12") (pintype "tri_state"))
      (node (ref "IC28") (pin "13") (pinfunction "5D_13") (pintype "input"))
      (node (ref "IC30") (pin "12") (pinfunction "5Q_12") (pintype "tri_state"))
      (node (ref "IC30") (pin "13") (pinfunction "5D_13") (pintype "input"))
      (node (ref "IC7") (pin "14") (pinfunction "B5_14") (pintype "bidirectional"))
      (node (ref "RN1") (pin "6") (pinfunction "1_6") (pintype "passive"))
    )
    (net (code "31") (name "ADATA5") (class "Default")
      (node (ref "IC10") (pin "14") (pinfunction "6D_14") (pintype "input"))
      (node (ref "IC10") (pin "15") (pinfunction "6Q_15") (pintype "tri_state"))
      (node (ref "IC12") (pin "13") (pinfunction "A2_13") (pintype "input"))
      (node (ref "IC15") (pin "14") (pinfunction "6D_14") (pintype "input"))
      (node (ref "IC15") (pin "15") (pinfunction "6Q_15") (pintype "tri_state"))
      (node (ref "IC17") (pin "14") (pinfunction "6D_14") (pintype "input"))
      (node (ref "IC17") (pin "15") (pinfunction "6Q_15") (pintype "tri_state"))
      (node (ref "IC21") (pin "14") (pinfunction "6D_14") (pintype "input"))
      (node (ref "IC21") (pin "15") (pinfunction "6Q_15") (pintype "tri_state"))
      (node (ref "IC23") (pin "14") (pinfunction "6D_14") (pintype "input"))
      (node (ref "IC23") (pin "15") (pinfunction "6Q_15") (pintype "tri_state"))
      (node (ref "IC26") (pin "14") (pinfunction "6D_14") (pintype "input"))
      (node (ref "IC26") (pin "15") (pinfunction "6Q_15") (pintype "tri_state"))
      (node (ref "IC28") (pin "14") (pinfunction "6D_14") (pintype "input"))
      (node (ref "IC28") (pin "15") (pinfunction "6Q_15") (pintype "tri_state"))
      (node (ref "IC30") (pin "14") (pinfunction "6D_14") (pintype "input"))
      (node (ref "IC30") (pin "15") (pinfunction "6Q_15") (pintype "tri_state"))
      (node (ref "IC7") (pin "13") (pinfunction "B6_13") (pintype "bidirectional"))
      (node (ref "RN1") (pin "7") (pinfunction "1_7") (pintype "passive"))
    )
    (net (code "32") (name "ADATA6") (class "Default")
      (node (ref "IC10") (pin "16") (pinfunction "7Q_16") (pintype "tri_state"))
      (node (ref "IC10") (pin "17") (pinfunction "7D_17") (pintype "input"))
      (node (ref "IC12") (pin "15") (pinfunction "A3_15") (pintype "input"))
      (node (ref "IC15") (pin "16") (pinfunction "7Q_16") (pintype "tri_state"))
      (node (ref "IC15") (pin "17") (pinfunction "7D_17") (pintype "input"))
      (node (ref "IC17") (pin "16") (pinfunction "7Q_16") (pintype "tri_state"))
      (node (ref "IC17") (pin "17") (pinfunction "7D_17") (pintype "input"))
      (node (ref "IC21") (pin "16") (pinfunction "7Q_16") (pintype "tri_state"))
      (node (ref "IC21") (pin "17") (pinfunction "7D_17") (pintype "input"))
      (node (ref "IC23") (pin "16") (pinfunction "7Q_16") (pintype "tri_state"))
      (node (ref "IC23") (pin "17") (pinfunction "7D_17") (pintype "input"))
      (node (ref "IC26") (pin "16") (pinfunction "7Q_16") (pintype "tri_state"))
      (node (ref "IC26") (pin "17") (pinfunction "7D_17") (pintype "input"))
      (node (ref "IC28") (pin "16") (pinfunction "7Q_16") (pintype "tri_state"))
      (node (ref "IC28") (pin "17") (pinfunction "7D_17") (pintype "input"))
      (node (ref "IC30") (pin "16") (pinfunction "7Q_16") (pintype "tri_state"))
      (node (ref "IC30") (pin "17") (pinfunction "7D_17") (pintype "input"))
      (node (ref "IC7") (pin "12") (pinfunction "B7_12") (pintype "bidirectional"))
      (node (ref "RN1") (pin "8") (pinfunction "1_8") (pintype "passive"))
    )
    (net (code "33") (name "ADATA7") (class "Default")
      (node (ref "IC10") (pin "18") (pinfunction "8D_18") (pintype "input"))
      (node (ref "IC10") (pin "19") (pinfunction "8Q_19") (pintype "tri_state"))
      (node (ref "IC12") (pin "17") (pinfunction "A4_17") (pintype "input"))
      (node (ref "IC15") (pin "18") (pinfunction "8D_18") (pintype "input"))
      (node (ref "IC15") (pin "19") (pinfunction "8Q_19") (pintype "tri_state"))
      (node (ref "IC17") (pin "18") (pinfunction "8D_18") (pintype "input"))
      (node (ref "IC17") (pin "19") (pinfunction "8Q_19") (pintype "tri_state"))
      (node (ref "IC21") (pin "18") (pinfunction "8D_18") (pintype "input"))
      (node (ref "IC21") (pin "19") (pinfunction "8Q_19") (pintype "tri_state"))
      (node (ref "IC23") (pin "18") (pinfunction "8D_18") (pintype "input"))
      (node (ref "IC23") (pin "19") (pinfunction "8Q_19") (pintype "tri_state"))
      (node (ref "IC26") (pin "18") (pinfunction "8D_18") (pintype "input"))
      (node (ref "IC26") (pin "19") (pinfunction "8Q_19") (pintype "tri_state"))
      (node (ref "IC28") (pin "18") (pinfunction "8D_18") (pintype "input"))
      (node (ref "IC28") (pin "19") (pinfunction "8Q_19") (pintype "tri_state"))
      (node (ref "IC30") (pin "18") (pinfunction "8D_18") (pintype "input"))
      (node (ref "IC30") (pin "19") (pinfunction "8Q_19") (pintype "tri_state"))
      (node (ref "IC7") (pin "11") (pinfunction "B8_11") (pintype "bidirectional"))
      (node (ref "RN1") (pin "9") (pinfunction "1_9") (pintype "passive"))
    )
    (net (code "34") (name "ADATA8") (class "Default")
      (node (ref "IC11") (pin "2") (pinfunction "A1_2") (pintype "input"))
      (node (ref "IC16") (pin "2") (pinfunction "1Q_2") (pintype "tri_state"))
      (node (ref "IC16") (pin "3") (pinfunction "1D_3") (pintype "input"))
      (node (ref "IC18") (pin "2") (pinfunction "1Q_2") (pintype "tri_state"))
      (node (ref "IC18") (pin "3") (pinfunction "1D_3") (pintype "input"))
      (node (ref "IC22") (pin "2") (pinfunction "1Q_2") (pintype "tri_state"))
      (node (ref "IC22") (pin "3") (pinfunction "1D_3") (pintype "input"))
      (node (ref "IC24") (pin "2") (pinfunction "1Q_2") (pintype "tri_state"))
      (node (ref "IC24") (pin "3") (pinfunction "1D_3") (pintype "input"))
      (node (ref "IC25") (pin "2") (pinfunction "1Q_2") (pintype "tri_state"))
      (node (ref "IC25") (pin "3") (pinfunction "1D_3") (pintype "input"))
      (node (ref "IC27") (pin "2") (pinfunction "1Q_2") (pintype "tri_state"))
      (node (ref "IC27") (pin "3") (pinfunction "1D_3") (pintype "input"))
      (node (ref "IC29") (pin "2") (pinfunction "1Q_2") (pintype "tri_state"))
      (node (ref "IC29") (pin "3") (pinfunction "1D_3") (pintype "input"))
      (node (ref "IC31") (pin "2") (pinfunction "1Q_2") (pintype "tri_state"))
      (node (ref "IC31") (pin "3") (pinfunction "1D_3") (pintype "input"))
      (node (ref "IC8") (pin "18") (pinfunction "B1_18") (pintype "bidirectional"))
      (node (ref "IC9") (pin "18") (pinfunction "B1_18") (pintype "bidirectional"))
      (node (ref "RN2") (pin "2") (pinfunction "1_2") (pintype "passive"))
    )
    (net (code "35") (name "ADATA9") (class "Default")
      (node (ref "IC11") (pin "4") (pinfunction "A2_4") (pintype "input"))
      (node (ref "IC16") (pin "4") (pinfunction "2D_4") (pintype "input"))
      (node (ref "IC16") (pin "5") (pinfunction "2Q_5") (pintype "tri_state"))
      (node (ref "IC18") (pin "4") (pinfunction "2D_4") (pintype "input"))
      (node (ref "IC18") (pin "5") (pinfunction "2Q_5") (pintype "tri_state"))
      (node (ref "IC22") (pin "4") (pinfunction "2D_4") (pintype "input"))
      (node (ref "IC22") (pin "5") (pinfunction "2Q_5") (pintype "tri_state"))
      (node (ref "IC24") (pin "4") (pinfunction "2D_4") (pintype "input"))
      (node (ref "IC24") (pin "5") (pinfunction "2Q_5") (pintype "tri_state"))
      (node (ref "IC25") (pin "4") (pinfunction "2D_4") (pintype "input"))
      (node (ref "IC25") (pin "5") (pinfunction "2Q_5") (pintype "tri_state"))
      (node (ref "IC27") (pin "4") (pinfunction "2D_4") (pintype "input"))
      (node (ref "IC27") (pin "5") (pinfunction "2Q_5") (pintype "tri_state"))
      (node (ref "IC29") (pin "4") (pinfunction "2D_4") (pintype "input"))
      (node (ref "IC29") (pin "5") (pinfunction "2Q_5") (pintype "tri_state"))
      (node (ref "IC31") (pin "4") (pinfunction "2D_4") (pintype "input"))
      (node (ref "IC31") (pin "5") (pinfunction "2Q_5") (pintype "tri_state"))
      (node (ref "IC8") (pin "17") (pinfunction "B2_17") (pintype "bidirectional"))
      (node (ref "IC9") (pin "17") (pinfunction "B2_17") (pintype "bidirectional"))
      (node (ref "RN2") (pin "3") (pinfunction "1_3") (pintype "passive"))
    )
    (net (code "36") (name "ADATA10") (class "Default")
      (node (ref "IC11") (pin "6") (pinfunction "A3_6") (pintype "input"))
      (node (ref "IC16") (pin "6") (pinfunction "3Q_6") (pintype "tri_state"))
      (node (ref "IC16") (pin "7") (pinfunction "3D_7") (pintype "input"))
      (node (ref "IC18") (pin "6") (pinfunction "3Q_6") (pintype "tri_state"))
      (node (ref "IC18") (pin "7") (pinfunction "3D_7") (pintype "input"))
      (node (ref "IC22") (pin "6") (pinfunction "3Q_6") (pintype "tri_state"))
      (node (ref "IC22") (pin "7") (pinfunction "3D_7") (pintype "input"))
      (node (ref "IC24") (pin "6") (pinfunction "3Q_6") (pintype "tri_state"))
      (node (ref "IC24") (pin "7") (pinfunction "3D_7") (pintype "input"))
      (node (ref "IC25") (pin "6") (pinfunction "3Q_6") (pintype "tri_state"))
      (node (ref "IC25") (pin "7") (pinfunction "3D_7") (pintype "input"))
      (node (ref "IC27") (pin "6") (pinfunction "3Q_6") (pintype "tri_state"))
      (node (ref "IC27") (pin "7") (pinfunction "3D_7") (pintype "input"))
      (node (ref "IC29") (pin "6") (pinfunction "3Q_6") (pintype "tri_state"))
      (node (ref "IC29") (pin "7") (pinfunction "3D_7") (pintype "input"))
      (node (ref "IC31") (pin "6") (pinfunction "3Q_6") (pintype "tri_state"))
      (node (ref "IC31") (pin "7") (pinfunction "3D_7") (pintype "input"))
      (node (ref "IC8") (pin "16") (pinfunction "B3_16") (pintype "bidirectional"))
      (node (ref "IC9") (pin "16") (pinfunction "B3_16") (pintype "bidirectional"))
      (node (ref "RN2") (pin "4") (pinfunction "1_4") (pintype "passive"))
    )
    (net (code "37") (name "ADATA11") (class "Default")
      (node (ref "IC11") (pin "8") (pinfunction "A4_8") (pintype "input"))
      (node (ref "IC16") (pin "8") (pinfunction "4D_8") (pintype "input"))
      (node (ref "IC16") (pin "9") (pinfunction "4Q_9") (pintype "tri_state"))
      (node (ref "IC18") (pin "8") (pinfunction "4D_8") (pintype "input"))
      (node (ref "IC18") (pin "9") (pinfunction "4Q_9") (pintype "tri_state"))
      (node (ref "IC22") (pin "8") (pinfunction "4D_8") (pintype "input"))
      (node (ref "IC22") (pin "9") (pinfunction "4Q_9") (pintype "tri_state"))
      (node (ref "IC24") (pin "8") (pinfunction "4D_8") (pintype "input"))
      (node (ref "IC24") (pin "9") (pinfunction "4Q_9") (pintype "tri_state"))
      (node (ref "IC25") (pin "8") (pinfunction "4D_8") (pintype "input"))
      (node (ref "IC25") (pin "9") (pinfunction "4Q_9") (pintype "tri_state"))
      (node (ref "IC27") (pin "8") (pinfunction "4D_8") (pintype "input"))
      (node (ref "IC27") (pin "9") (pinfunction "4Q_9") (pintype "tri_state"))
      (node (ref "IC29") (pin "8") (pinfunction "4D_8") (pintype "input"))
      (node (ref "IC29") (pin "9") (pinfunction "4Q_9") (pintype "tri_state"))
      (node (ref "IC31") (pin "8") (pinfunction "4D_8") (pintype "input"))
      (node (ref "IC31") (pin "9") (pinfunction "4Q_9") (pintype "tri_state"))
      (node (ref "IC8") (pin "15") (pinfunction "B4_15") (pintype "bidirectional"))
      (node (ref "IC9") (pin "15") (pinfunction "B4_15") (pintype "bidirectional"))
      (node (ref "RN2") (pin "5") (pinfunction "1_5") (pintype "passive"))
    )
    (net (code "38") (name "ADATA12") (class "Default")
      (node (ref "IC11") (pin "11") (pinfunction "A1_11") (pintype "input"))
      (node (ref "IC16") (pin "12") (pinfunction "5Q_12") (pintype "tri_state"))
      (node (ref "IC16") (pin "13") (pinfunction "5D_13") (pintype "input"))
      (node (ref "IC18") (pin "12") (pinfunction "5Q_12") (pintype "tri_state"))
      (node (ref "IC18") (pin "13") (pinfunction "5D_13") (pintype "input"))
      (node (ref "IC22") (pin "12") (pinfunction "5Q_12") (pintype "tri_state"))
      (node (ref "IC22") (pin "13") (pinfunction "5D_13") (pintype "input"))
      (node (ref "IC24") (pin "12") (pinfunction "5Q_12") (pintype "tri_state"))
      (node (ref "IC24") (pin "13") (pinfunction "5D_13") (pintype "input"))
      (node (ref "IC25") (pin "12") (pinfunction "5Q_12") (pintype "tri_state"))
      (node (ref "IC25") (pin "13") (pinfunction "5D_13") (pintype "input"))
      (node (ref "IC27") (pin "12") (pinfunction "5Q_12") (pintype "tri_state"))
      (node (ref "IC27") (pin "13") (pinfunction "5D_13") (pintype "input"))
      (node (ref "IC29") (pin "12") (pinfunction "5Q_12") (pintype "tri_state"))
      (node (ref "IC29") (pin "13") (pinfunction "5D_13") (pintype "input"))
      (node (ref "IC31") (pin "12") (pinfunction "5Q_12") (pintype "tri_state"))
      (node (ref "IC31") (pin "13") (pinfunction "5D_13") (pintype "input"))
      (node (ref "IC8") (pin "14") (pinfunction "B5_14") (pintype "bidirectional"))
      (node (ref "IC9") (pin "14") (pinfunction "B5_14") (pintype "bidirectional"))
      (node (ref "RN2") (pin "6") (pinfunction "1_6") (pintype "passive"))
    )
    (net (code "39") (name "ADATA13") (class "Default")
      (node (ref "IC11") (pin "13") (pinfunction "A2_13") (pintype "input"))
      (node (ref "IC16") (pin "14") (pinfunction "6D_14") (pintype "input"))
      (node (ref "IC16") (pin "15") (pinfunction "6Q_15") (pintype "tri_state"))
      (node (ref "IC18") (pin "14") (pinfunction "6D_14") (pintype "input"))
      (node (ref "IC18") (pin "15") (pinfunction "6Q_15") (pintype "tri_state"))
      (node (ref "IC22") (pin "14") (pinfunction "6D_14") (pintype "input"))
      (node (ref "IC22") (pin "15") (pinfunction "6Q_15") (pintype "tri_state"))
      (node (ref "IC24") (pin "14") (pinfunction "6D_14") (pintype "input"))
      (node (ref "IC24") (pin "15") (pinfunction "6Q_15") (pintype "tri_state"))
      (node (ref "IC25") (pin "14") (pinfunction "6D_14") (pintype "input"))
      (node (ref "IC25") (pin "15") (pinfunction "6Q_15") (pintype "tri_state"))
      (node (ref "IC27") (pin "14") (pinfunction "6D_14") (pintype "input"))
      (node (ref "IC27") (pin "15") (pinfunction "6Q_15") (pintype "tri_state"))
      (node (ref "IC29") (pin "14") (pinfunction "6D_14") (pintype "input"))
      (node (ref "IC29") (pin "15") (pinfunction "6Q_15") (pintype "tri_state"))
      (node (ref "IC31") (pin "14") (pinfunction "6D_14") (pintype "input"))
      (node (ref "IC31") (pin "15") (pinfunction "6Q_15") (pintype "tri_state"))
      (node (ref "IC8") (pin "13") (pinfunction "B6_13") (pintype "bidirectional"))
      (node (ref "IC9") (pin "13") (pinfunction "B6_13") (pintype "bidirectional"))
      (node (ref "RN2") (pin "7") (pinfunction "1_7") (pintype "passive"))
    )
    (net (code "40") (name "ADATA14") (class "Default")
      (node (ref "IC11") (pin "15") (pinfunction "A3_15") (pintype "input"))
      (node (ref "IC16") (pin "16") (pinfunction "7Q_16") (pintype "tri_state"))
      (node (ref "IC16") (pin "17") (pinfunction "7D_17") (pintype "input"))
      (node (ref "IC18") (pin "16") (pinfunction "7Q_16") (pintype "tri_state"))
      (node (ref "IC18") (pin "17") (pinfunction "7D_17") (pintype "input"))
      (node (ref "IC22") (pin "16") (pinfunction "7Q_16") (pintype "tri_state"))
      (node (ref "IC22") (pin "17") (pinfunction "7D_17") (pintype "input"))
      (node (ref "IC24") (pin "16") (pinfunction "7Q_16") (pintype "tri_state"))
      (node (ref "IC24") (pin "17") (pinfunction "7D_17") (pintype "input"))
      (node (ref "IC25") (pin "16") (pinfunction "7Q_16") (pintype "tri_state"))
      (node (ref "IC25") (pin "17") (pinfunction "7D_17") (pintype "input"))
      (node (ref "IC27") (pin "16") (pinfunction "7Q_16") (pintype "tri_state"))
      (node (ref "IC27") (pin "17") (pinfunction "7D_17") (pintype "input"))
      (node (ref "IC29") (pin "16") (pinfunction "7Q_16") (pintype "tri_state"))
      (node (ref "IC29") (pin "17") (pinfunction "7D_17") (pintype "input"))
      (node (ref "IC31") (pin "16") (pinfunction "7Q_16") (pintype "tri_state"))
      (node (ref "IC31") (pin "17") (pinfunction "7D_17") (pintype "input"))
      (node (ref "IC8") (pin "12") (pinfunction "B7_12") (pintype "bidirectional"))
      (node (ref "IC9") (pin "12") (pinfunction "B7_12") (pintype "bidirectional"))
      (node (ref "RN2") (pin "8") (pinfunction "1_8") (pintype "passive"))
    )
    (net (code "41") (name "ADATA15") (class "Default")
      (node (ref "IC11") (pin "17") (pinfunction "A4_17") (pintype "input"))
      (node (ref "IC16") (pin "18") (pinfunction "8D_18") (pintype "input"))
      (node (ref "IC16") (pin "19") (pinfunction "8Q_19") (pintype "tri_state"))
      (node (ref "IC18") (pin "18") (pinfunction "8D_18") (pintype "input"))
      (node (ref "IC18") (pin "19") (pinfunction "8Q_19") (pintype "tri_state"))
      (node (ref "IC22") (pin "18") (pinfunction "8D_18") (pintype "input"))
      (node (ref "IC22") (pin "19") (pinfunction "8Q_19") (pintype "tri_state"))
      (node (ref "IC24") (pin "18") (pinfunction "8D_18") (pintype "input"))
      (node (ref "IC24") (pin "19") (pinfunction "8Q_19") (pintype "tri_state"))
      (node (ref "IC25") (pin "18") (pinfunction "8D_18") (pintype "input"))
      (node (ref "IC25") (pin "19") (pinfunction "8Q_19") (pintype "tri_state"))
      (node (ref "IC27") (pin "18") (pinfunction "8D_18") (pintype "input"))
      (node (ref "IC27") (pin "19") (pinfunction "8Q_19") (pintype "tri_state"))
      (node (ref "IC29") (pin "18") (pinfunction "8D_18") (pintype "input"))
      (node (ref "IC29") (pin "19") (pinfunction "8Q_19") (pintype "tri_state"))
      (node (ref "IC31") (pin "18") (pinfunction "8D_18") (pintype "input"))
      (node (ref "IC31") (pin "19") (pinfunction "8Q_19") (pintype "tri_state"))
      (node (ref "IC8") (pin "11") (pinfunction "B8_11") (pintype "bidirectional"))
      (node (ref "IC9") (pin "11") (pinfunction "B8_11") (pintype "bidirectional"))
      (node (ref "RN2") (pin "9") (pinfunction "1_9") (pintype "passive"))
    )
    (net (code "42") (name "ADDR0") (class "Default")
      (node (ref "X2") (pin "A3") (pinfunction "B_A3") (pintype "passive"))
    )
    (net (code "43") (name "ADDR1") (class "Default")
      (node (ref "X2") (pin "A4") (pinfunction "B_A4") (pintype "passive"))
    )
    (net (code "44") (name "ADDR2") (class "Default")
      (node (ref "X2") (pin "A5") (pinfunction "B_A5") (pintype "passive"))
    )
    (net (code "45") (name "ADDR3") (class "Default")
      (node (ref "X2") (pin "A6") (pinfunction "B_A6") (pintype "passive"))
    )
    (net (code "46") (name "ADDR4") (class "Default")
      (node (ref "X2") (pin "A7") (pinfunction "B_A7") (pintype "passive"))
    )
    (net (code "47") (name "ADDR5") (class "Default")
      (node (ref "X2") (pin "A8") (pinfunction "B_A8") (pintype "passive"))
    )
    (net (code "48") (name "ADDR6") (class "Default")
      (node (ref "X2") (pin "A9") (pinfunction "B_A9") (pintype "passive"))
    )
    (net (code "49") (name "ADDR7") (class "Default")
      (node (ref "X2") (pin "A10") (pinfunction "B_A10") (pintype "passive"))
    )
    (net (code "50") (name "ADDR8") (class "Default")
      (node (ref "X2") (pin "A11") (pinfunction "B_A11") (pintype "passive"))
    )
    (net (code "51") (name "ADDR9") (class "Default")
      (node (ref "X2") (pin "A12") (pinfunction "B_A12") (pintype "passive"))
    )
    (net (code "52") (name "ADDR10") (class "Default")
      (node (ref "X2") (pin "A13") (pinfunction "B_A13") (pintype "passive"))
    )
    (net (code "53") (name "ADDR11") (class "Default")
      (node (ref "X2") (pin "A14") (pinfunction "B_A14") (pintype "passive"))
    )
    (net (code "54") (name "ADDR12") (class "Default")
      (node (ref "X2") (pin "A15") (pinfunction "B_A15") (pintype "passive"))
    )
    (net (code "55") (name "ADDR13") (class "Default")
      (node (ref "X2") (pin "A16") (pinfunction "B_A16") (pintype "passive"))
    )
    (net (code "56") (name "ADDR14") (class "Default")
      (node (ref "X2") (pin "A17") (pinfunction "B_A17") (pintype "passive"))
    )
    (net (code "57") (name "ADDR15") (class "Default")
      (node (ref "X2") (pin "A18") (pinfunction "B_A18") (pintype "passive"))
    )
    (net (code "58") (name "ALU-FUNC") (class "Default")
      (node (ref "X2") (pin "C15") (pinfunction "B_C15") (pintype "passive"))
    )
    (net (code "59") (name "ALU0") (class "Default")
      (node (ref "X2") (pin "C16") (pinfunction "B_C16") (pintype "passive"))
    )
    (net (code "60") (name "ALU1") (class "Default")
      (node (ref "X2") (pin "C17") (pinfunction "B_C17") (pintype "passive"))
    )
    (net (code "61") (name "ALU2") (class "Default")
      (node (ref "X2") (pin "C18") (pinfunction "B_C18") (pintype "passive"))
    )
    (net (code "62") (name "ALU3") (class "Default")
      (node (ref "X2") (pin "C19") (pinfunction "B_C19") (pintype "passive"))
    )
    (net (code "63") (name "BR-COND") (class "Default")
      (node (ref "X2") (pin "C24") (pinfunction "B_C24") (pintype "passive"))
    )
    (net (code "64") (name "BUS-DIR") (class "Default")
      (node (ref "IC1") (pin "10") (pinfunction "O_10") (pintype "output"))
      (node (ref "IC7") (pin "1") (pinfunction "DIR_1") (pintype "input"))
      (node (ref "IC8") (pin "1") (pinfunction "DIR_1") (pintype "input"))
      (node (ref "IC9") (pin "1") (pinfunction "DIR_1") (pintype "input"))
    )
    (net (code "65") (name "CLK0H") (class "Default")
      (node (ref "IC14") (pin "4") (pinfunction "O_4") (pintype "output"))
      (node (ref "IC16") (pin "11") (pinfunction "CLK_11") (pintype "input"))
      (node (ref "IC34") (pin "15") (pinfunction "A3_15") (pintype "input"))
    )
    (net (code "66") (name "CLK0L") (class "Default")
      (node (ref "IC14") (pin "1") (pinfunction "O_1") (pintype "output"))
      (node (ref "IC15") (pin "11") (pinfunction "CLK_11") (pintype "input"))
      (node (ref "IC34") (pin "17") (pinfunction "A4_17") (pintype "input"))
    )
    (net (code "67") (name "CLK1H") (class "Default")
      (node (ref "IC14") (pin "13") (pinfunction "O_13") (pintype "output"))
      (node (ref "IC18") (pin "11") (pinfunction "CLK_11") (pintype "input"))
      (node (ref "IC34") (pin "11") (pinfunction "A1_11") (pintype "input"))
    )
    (net (code "68") (name "CLK1L") (class "Default")
      (node (ref "IC14") (pin "10") (pinfunction "O_10") (pintype "output"))
      (node (ref "IC17") (pin "11") (pinfunction "CLK_11") (pintype "input"))
      (node (ref "IC34") (pin "13") (pinfunction "A2_13") (pintype "input"))
    )
    (net (code "69") (name "CLK2H") (class "Default")
      (node (ref "IC20") (pin "4") (pinfunction "O_4") (pintype "output"))
      (node (ref "IC22") (pin "11") (pinfunction "CLK_11") (pintype "input"))
      (node (ref "IC33") (pin "4") (pinfunction "A2_4") (pintype "input"))
    )
    (net (code "70") (name "CLK2L") (class "Default")
      (node (ref "IC20") (pin "1") (pinfunction "O_1") (pintype "output"))
      (node (ref "IC21") (pin "11") (pinfunction "CLK_11") (pintype "input"))
      (node (ref "IC33") (pin "2") (pinfunction "A1_2") (pintype "input"))
    )
    (net (code "71") (name "CLK3H") (class "Default")
      (node (ref "IC20") (pin "13") (pinfunction "O_13") (pintype "output"))
      (node (ref "IC24") (pin "11") (pinfunction "CLK_11") (pintype "input"))
      (node (ref "IC33") (pin "8") (pinfunction "A4_8") (pintype "input"))
    )
    (net (code "72") (name "CLK3L") (class "Default")
      (node (ref "IC20") (pin "10") (pinfunction "O_10") (pintype "output"))
      (node (ref "IC23") (pin "11") (pinfunction "CLK_11") (pintype "input"))
      (node (ref "IC33") (pin "6") (pinfunction "A3_6") (pintype "input"))
    )
    (net (code "73") (name "CLK4H") (class "Default")
      (node (ref "IC25") (pin "11") (pinfunction "CLK_11") (pintype "input"))
      (node (ref "IC34") (pin "6") (pinfunction "A3_6") (pintype "input"))
      (node (ref "IC35") (pin "4") (pinfunction "O_4") (pintype "output"))
    )
    (net (code "74") (name "CLK4L") (class "Default")
      (node (ref "IC10") (pin "11") (pinfunction "CLK_11") (pintype "input"))
      (node (ref "IC34") (pin "8") (pinfunction "A4_8") (pintype "input"))
      (node (ref "IC35") (pin "1") (pinfunction "O_1") (pintype "output"))
    )
    (net (code "75") (name "CLK5H") (class "Default")
      (node (ref "IC29") (pin "11") (pinfunction "CLK_11") (pintype "input"))
      (node (ref "IC34") (pin "2") (pinfunction "A1_2") (pintype "input"))
      (node (ref "IC35") (pin "13") (pinfunction "O_13") (pintype "output"))
    )
    (net (code "76") (name "CLK5L") (class "Default")
      (node (ref "IC28") (pin "11") (pinfunction "CLK_11") (pintype "input"))
      (node (ref "IC34") (pin "4") (pinfunction "A2_4") (pintype "input"))
      (node (ref "IC35") (pin "10") (pinfunction "O_10") (pintype "output"))
    )
    (net (code "77") (name "CLK6H") (class "Default")
      (node (ref "IC27") (pin "11") (pinfunction "CLK_11") (pintype "input"))
      (node (ref "IC33") (pin "13") (pinfunction "A2_13") (pintype "input"))
      (node (ref "IC38") (pin "4") (pinfunction "O_4") (pintype "output"))
    )
    (net (code "78") (name "CLK6L") (class "Default")
      (node (ref "IC26") (pin "11") (pinfunction "CLK_11") (pintype "input"))
      (node (ref "IC33") (pin "11") (pinfunction "A1_11") (pintype "input"))
      (node (ref "IC38") (pin "1") (pinfunction "O_1") (pintype "output"))
    )
    (net (code "79") (name "CLK7H") (class "Default")
      (node (ref "IC31") (pin "11") (pinfunction "CLK_11") (pintype "input"))
      (node (ref "IC33") (pin "17") (pinfunction "A4_17") (pintype "input"))
      (node (ref "IC38") (pin "13") (pinfunction "O_13") (pintype "output"))
    )
    (net (code "80") (name "CLK7L") (class "Default")
      (node (ref "IC30") (pin "11") (pinfunction "CLK_11") (pintype "input"))
      (node (ref "IC33") (pin "15") (pinfunction "A3_15") (pintype "input"))
      (node (ref "IC38") (pin "10") (pinfunction "O_10") (pintype "output"))
    )
    (net (code "81") (name "DATA0") (class "Default")
      (node (ref "IC7") (pin "2") (pinfunction "A1_2") (pintype "bidirectional"))
      (node (ref "IC9") (pin "2") (pinfunction "A1_2") (pintype "bidirectional"))
      (node (ref "X2") (pin "A19") (pinfunction "B_A19") (pintype "passive"))
    )
    (net (code "82") (name "DATA1") (class "Default")
      (node (ref "IC7") (pin "3") (pinfunction "A2_3") (pintype "bidirectional"))
      (node (ref "IC9") (pin "3") (pinfunction "A2_3") (pintype "bidirectional"))
      (node (ref "X2") (pin "A20") (pinfunction "B_A20") (pintype "passive"))
    )
    (net (code "83") (name "DATA2") (class "Default")
      (node (ref "IC7") (pin "4") (pinfunction "A3_4") (pintype "bidirectional"))
      (node (ref "IC9") (pin "4") (pinfunction "A3_4") (pintype "bidirectional"))
      (node (ref "X2") (pin "A21") (pinfunction "B_A21") (pintype "passive"))
    )
    (net (code "84") (name "DATA3") (class "Default")
      (node (ref "IC7") (pin "5") (pinfunction "A4_5") (pintype "bidirectional"))
      (node (ref "IC9") (pin "5") (pinfunction "A4_5") (pintype "bidirectional"))
      (node (ref "X2") (pin "A22") (pinfunction "B_A22") (pintype "passive"))
    )
    (net (code "85") (name "DATA4") (class "Default")
      (node (ref "IC7") (pin "6") (pinfunction "A5_6") (pintype "bidirectional"))
      (node (ref "IC9") (pin "6") (pinfunction "A5_6") (pintype "bidirectional"))
      (node (ref "X2") (pin "A23") (pinfunction "B_A23") (pintype "passive"))
    )
    (net (code "86") (name "DATA5") (class "Default")
      (node (ref "IC7") (pin "7") (pinfunction "A6_7") (pintype "bidirectional"))
      (node (ref "IC9") (pin "7") (pinfunction "A6_7") (pintype "bidirectional"))
      (node (ref "X2") (pin "A24") (pinfunction "B_A24") (pintype "passive"))
    )
    (net (code "87") (name "DATA6") (class "Default")
      (node (ref "IC7") (pin "8") (pinfunction "A7_8") (pintype "bidirectional"))
      (node (ref "IC9") (pin "8") (pinfunction "A7_8") (pintype "bidirectional"))
      (node (ref "X2") (pin "A25") (pinfunction "B_A25") (pintype "passive"))
    )
    (net (code "88") (name "DATA7") (class "Default")
      (node (ref "IC7") (pin "9") (pinfunction "A8_9") (pintype "bidirectional"))
      (node (ref "IC9") (pin "9") (pinfunction "A8_9") (pintype "bidirectional"))
      (node (ref "X2") (pin "A26") (pinfunction "B_A26") (pintype "passive"))
    )
    (net (code "89") (name "DATA8") (class "Default")
      (node (ref "IC8") (pin "2") (pinfunction "A1_2") (pintype "bidirectional"))
      (node (ref "X2") (pin "A27") (pinfunction "B_A27") (pintype "passive"))
    )
    (net (code "90") (name "DATA9") (class "Default")
      (node (ref "IC8") (pin "3") (pinfunction "A2_3") (pintype "bidirectional"))
      (node (ref "X2") (pin "A28") (pinfunction "B_A28") (pintype "passive"))
    )
    (net (code "91") (name "DATA10") (class "Default")
      (node (ref "IC8") (pin "4") (pinfunction "A3_4") (pintype "bidirectional"))
      (node (ref "X2") (pin "A29") (pinfunction "B_A29") (pintype "passive"))
    )
    (net (code "92") (name "DATA11") (class "Default")
      (node (ref "IC8") (pin "5") (pinfunction "A4_5") (pintype "bidirectional"))
      (node (ref "X2") (pin "A30") (pinfunction "B_A30") (pintype "passive"))
    )
    (net (code "93") (name "DATA12") (class "Default")
      (node (ref "IC8") (pin "6") (pinfunction "A5_6") (pintype "bidirectional"))
      (node (ref "X2") (pin "B3") (pinfunction "B_B3") (pintype "passive"))
    )
    (net (code "94") (name "DATA13") (class "Default")
      (node (ref "IC8") (pin "7") (pinfunction "A6_7") (pintype "bidirectional"))
      (node (ref "X2") (pin "B4") (pinfunction "B_B4") (pintype "passive"))
    )
    (net (code "95") (name "DATA14") (class "Default")
      (node (ref "IC8") (pin "8") (pinfunction "A7_8") (pintype "bidirectional"))
      (node (ref "X2") (pin "B5") (pinfunction "B_B5") (pintype "passive"))
    )
    (net (code "96") (name "DATA15") (class "Default")
      (node (ref "IC8") (pin "9") (pinfunction "A8_9") (pintype "bidirectional"))
      (node (ref "X2") (pin "B6") (pinfunction "B_B6") (pintype "passive"))
    )
    (net (code "97") (name "FP-ADATA0") (class "Default")
      (node (ref "IC12") (pin "18") (pinfunction "Y1_18") (pintype "tri_state"))
      (node (ref "JP6") (pin "3") (pinfunction "3_3") (pintype "passive"))
    )
    (net (code "98") (name "FP-ADATA1") (class "Default")
      (node (ref "IC12") (pin "16") (pinfunction "Y2_16") (pintype "tri_state"))
      (node (ref "JP6") (pin "5") (pinfunction "5_5") (pintype "passive"))
    )
    (net (code "99") (name "FP-ADATA2") (class "Default")
      (node (ref "IC12") (pin "14") (pinfunction "Y3_14") (pintype "tri_state"))
      (node (ref "JP6") (pin "7") (pinfunction "7_7") (pintype "passive"))
    )
    (net (code "100") (name "FP-ADATA3") (class "Default")
      (node (ref "IC12") (pin "12") (pinfunction "Y4_12") (pintype "tri_state"))
      (node (ref "JP6") (pin "9") (pinfunction "9_9") (pintype "passive"))
    )
    (net (code "101") (name "FP-ADATA4") (class "Default")
      (node (ref "IC12") (pin "9") (pinfunction "Y1_9") (pintype "tri_state"))
      (node (ref "JP6") (pin "11") (pinfunction "11_11") (pintype "passive"))
    )
    (net (code "102") (name "FP-ADATA5") (class "Default")
      (node (ref "IC12") (pin "7") (pinfunction "Y2_7") (pintype "tri_state"))
      (node (ref "JP6") (pin "13") (pinfunction "13_13") (pintype "passive"))
    )
    (net (code "103") (name "FP-ADATA6") (class "Default")
      (node (ref "IC12") (pin "5") (pinfunction "Y3_5") (pintype "tri_state"))
      (node (ref "JP6") (pin "15") (pinfunction "15_15") (pintype "passive"))
    )
    (net (code "104") (name "FP-ADATA7") (class "Default")
      (node (ref "IC12") (pin "3") (pinfunction "Y4_3") (pintype "tri_state"))
      (node (ref "JP6") (pin "17") (pinfunction "17_17") (pintype "passive"))
    )
    (net (code "105") (name "FP-ADATA8") (class "Default")
      (node (ref "IC11") (pin "18") (pinfunction "Y1_18") (pintype "tri_state"))
      (node (ref "JP6") (pin "4") (pinfunction "4_4") (pintype "passive"))
    )
    (net (code "106") (name "FP-ADATA9") (class "Default")
      (node (ref "IC11") (pin "16") (pinfunction "Y2_16") (pintype "tri_state"))
      (node (ref "JP6") (pin "6") (pinfunction "6_6") (pintype "passive"))
    )
    (net (code "107") (name "FP-ADATA10") (class "Default")
      (node (ref "IC11") (pin "14") (pinfunction "Y3_14") (pintype "tri_state"))
      (node (ref "JP6") (pin "8") (pinfunction "8_8") (pintype "passive"))
    )
    (net (code "108") (name "FP-ADATA11") (class "Default")
      (node (ref "IC11") (pin "12") (pinfunction "Y4_12") (pintype "tri_state"))
      (node (ref "JP6") (pin "10") (pinfunction "10_10") (pintype "passive"))
    )
    (net (code "109") (name "FP-ADATA12") (class "Default")
      (node (ref "IC11") (pin "9") (pinfunction "Y1_9") (pintype "tri_state"))
      (node (ref "JP6") (pin "12") (pinfunction "12_12") (pintype "passive"))
    )
    (net (code "110") (name "FP-ADATA13") (class "Default")
      (node (ref "IC11") (pin "7") (pinfunction "Y2_7") (pintype "tri_state"))
      (node (ref "JP6") (pin "14") (pinfunction "14_14") (pintype "passive"))
    )
    (net (code "111") (name "FP-ADATA14") (class "Default")
      (node (ref "IC11") (pin "5") (pinfunction "Y3_5") (pintype "tri_state"))
      (node (ref "JP6") (pin "16") (pinfunction "16_16") (pintype "passive"))
    )
    (net (code "112") (name "FP-ADATA15") (class "Default")
      (node (ref "IC11") (pin "3") (pinfunction "Y4_3") (pintype "tri_state"))
      (node (ref "JP6") (pin "18") (pinfunction "18_18") (pintype "passive"))
    )
    (net (code "113") (name "FP-CLK0H") (class "Default")
      (node (ref "IC34") (pin "5") (pinfunction "Y3_5") (pintype "tri_state"))
      (node (ref "JP6") (pin "23") (pinfunction "23_23") (pintype "passive"))
    )
    (net (code "114") (name "FP-CLK0L") (class "Default")
      (node (ref "IC34") (pin "3") (pinfunction "Y4_3") (pintype "tri_state"))
      (node (ref "JP6") (pin "25") (pinfunction "25_25") (pintype "passive"))
    )
    (net (code "115") (name "FP-CLK1H") (class "Default")
      (node (ref "IC34") (pin "9") (pinfunction "Y1_9") (pintype "tri_state"))
      (node (ref "JP6") (pin "19") (pinfunction "19_19") (pintype "passive"))
    )
    (net (code "116") (name "FP-CLK1L") (class "Default")
      (node (ref "IC34") (pin "7") (pinfunction "Y2_7") (pintype "tri_state"))
      (node (ref "JP6") (pin "21") (pinfunction "21_21") (pintype "passive"))
    )
    (net (code "117") (name "FP-CLK2H") (class "Default")
      (node (ref "IC33") (pin "16") (pinfunction "Y2_16") (pintype "tri_state"))
      (node (ref "JP6") (pin "24") (pinfunction "24_24") (pintype "passive"))
    )
    (net (code "118") (name "FP-CLK2L") (class "Default")
      (node (ref "IC33") (pin "18") (pinfunction "Y1_18") (pintype "tri_state"))
      (node (ref "JP6") (pin "26") (pinfunction "26_26") (pintype "passive"))
    )
    (net (code "119") (name "FP-CLK3H") (class "Default")
      (node (ref "IC33") (pin "12") (pinfunction "Y4_12") (pintype "tri_state"))
      (node (ref "JP6") (pin "20") (pinfunction "20_20") (pintype "passive"))
    )
    (net (code "120") (name "FP-CLK3L") (class "Default")
      (node (ref "IC33") (pin "14") (pinfunction "Y3_14") (pintype "tri_state"))
      (node (ref "JP6") (pin "22") (pinfunction "22_22") (pintype "passive"))
    )
    (net (code "121") (name "FP-CLK4H") (class "Default")
      (node (ref "IC34") (pin "14") (pinfunction "Y3_14") (pintype "tri_state"))
      (node (ref "JP6") (pin "31") (pinfunction "31_31") (pintype "passive"))
    )
    (net (code "122") (name "FP-CLK4L") (class "Default")
      (node (ref "IC34") (pin "12") (pinfunction "Y4_12") (pintype "tri_state"))
      (node (ref "JP6") (pin "33") (pinfunction "33_33") (pintype "passive"))
    )
    (net (code "123") (name "FP-CLK5H") (class "Default")
      (node (ref "IC34") (pin "18") (pinfunction "Y1_18") (pintype "tri_state"))
      (node (ref "JP6") (pin "27") (pinfunction "27_27") (pintype "passive"))
    )
    (net (code "124") (name "FP-CLK5L") (class "Default")
      (node (ref "IC34") (pin "16") (pinfunction "Y2_16") (pintype "tri_state"))
      (node (ref "JP6") (pin "29") (pinfunction "29_29") (pintype "passive"))
    )
    (net (code "125") (name "FP-CLK6H") (class "Default")
      (node (ref "IC33") (pin "7") (pinfunction "Y2_7") (pintype "tri_state"))
      (node (ref "JP6") (pin "32") (pinfunction "32_32") (pintype "passive"))
    )
    (net (code "126") (name "FP-CLK6L") (class "Default")
      (node (ref "IC33") (pin "9") (pinfunction "Y1_9") (pintype "tri_state"))
      (node (ref "JP6") (pin "34") (pinfunction "34_34") (pintype "passive"))
    )
    (net (code "127") (name "FP-CLK7H") (class "Default")
      (node (ref "IC33") (pin "3") (pinfunction "Y4_3") (pintype "tri_state"))
      (node (ref "JP6") (pin "28") (pinfunction "28_28") (pintype "passive"))
    )
    (net (code "128") (name "FP-CLK7L") (class "Default")
      (node (ref "IC33") (pin "5") (pinfunction "Y3_5") (pintype "tri_state"))
      (node (ref "JP6") (pin "30") (pinfunction "30_30") (pintype "passive"))
    )
    (net (code "129") (name "GND") (class "Default")
      (node (ref "C1") (pin "2") (pinfunction "2_2") (pintype "passive"))
      (node (ref "C10") (pin "2") (pinfunction "2_2") (pintype "passive"))
      (node (ref "C11") (pin "2") (pinfunction "2_2") (pintype "passive"))
      (node (ref "C12") (pin "2") (pinfunction "2_2") (pintype "passive"))
      (node (ref "C13") (pin "2") (pinfunction "2_2") (pintype "passive"))
      (node (ref "C14") (pin "2") (pinfunction "2_2") (pintype "passive"))
      (node (ref "C15") (pin "2") (pinfunction "2_2") (pintype "passive"))
      (node (ref "C16") (pin "2") (pinfunction "2_2") (pintype "passive"))
      (node (ref "C17") (pin "2") (pinfunction "2_2") (pintype "passive"))
      (node (ref "C18") (pin "2") (pinfunction "2_2") (pintype "passive"))
      (node (ref "C19") (pin "2") (pinfunction "2_2") (pintype "passive"))
      (node (ref "C2") (pin "2") (pinfunction "2_2") (pintype "passive"))
      (node (ref "C20") (pin "2") (pinfunction "2_2") (pintype "passive"))
      (node (ref "C21") (pin "2") (pinfunction "2_2") (pintype "passive"))
      (node (ref "C22") (pin "2") (pinfunction "2_2") (pintype "passive"))
      (node (ref "C23") (pin "2") (pinfunction "2_2") (pintype "passive"))
      (node (ref "C24") (pin "2") (pinfunction "2_2") (pintype "passive"))
      (node (ref "C25") (pin "2") (pinfunction "2_2") (pintype "passive"))
      (node (ref "C26") (pin "2") (pinfunction "2_2") (pintype "passive"))
      (node (ref "C27") (pin "2") (pinfunction "2_2") (pintype "passive"))
      (node (ref "C28") (pin "2") (pinfunction "2_2") (pintype "passive"))
      (node (ref "C29") (pin "2") (pinfunction "2_2") (pintype "passive"))
      (node (ref "C3") (pin "2") (pinfunction "2_2") (pintype "passive"))
      (node (ref "C30") (pin "2") (pinfunction "2_2") (pintype "passive"))
      (node (ref "C31") (pin "2") (pinfunction "2_2") (pintype "passive"))
      (node (ref "C32") (pin "2") (pinfunction "2_2") (pintype "passive"))
      (node (ref "C33") (pin "2") (pinfunction "2_2") (pintype "passive"))
      (node (ref "C34") (pin "2") (pinfunction "2_2") (pintype "passive"))
      (node (ref "C35") (pin "2") (pinfunction "2_2") (pintype "passive"))
      (node (ref "C36") (pin "2") (pinfunction "2_2") (pintype "passive"))
      (node (ref "C37") (pin "2") (pinfunction "2_2") (pintype "passive"))
      (node (ref "C4") (pin "2") (pinfunction "2_2") (pintype "passive"))
      (node (ref "C5") (pin "2") (pinfunction "2_2") (pintype "passive"))
      (node (ref "C6") (pin "2") (pinfunction "2_2") (pintype "passive"))
      (node (ref "C7") (pin "2") (pinfunction "2_2") (pintype "passive"))
      (node (ref "C8") (pin "2") (pinfunction "2_2") (pintype "passive"))
      (node (ref "C9") (pin "2") (pinfunction "2_2") (pintype "passive"))
      (node (ref "IC5") (pin "10") (pinfunction "I1_10") (pintype "input"))
      (node (ref "IC5") (pin "12") (pinfunction "I0_12") (pintype "input"))
      (node (ref "IC5") (pin "13") (pinfunction "I1_13") (pintype "input"))
      (node (ref "IC5") (pin "9") (pinfunction "I0_9") (pintype "input"))
      (node (ref "J1") (pin "2") (pinfunction "2_2") (pintype "passive"))
      (node (ref "JP6") (pin "39") (pinfunction "39_39") (pintype "passive"))
      (node (ref "JP6") (pin "40") (pinfunction "40_40") (pintype "passive"))
      (node (ref "PWR") (pin "K") (pinfunction "C_K") (pintype "passive"))
      (node (ref "X2") (pin "A1") (pinfunction "B_A1") (pintype "passive"))
      (node (ref "X2") (pin "A32") (pinfunction "B_A32") (pintype "passive"))
      (node (ref "X2") (pin "B1") (pinfunction "B_B1") (pintype "passive"))
      (node (ref "X2") (pin "B32") (pinfunction "B_B32") (pintype "passive"))
      (node (ref "X2") (pin "C1") (pinfunction "B_C1") (pintype "passive"))
      (node (ref "X2") (pin "C32") (pinfunction "B_C32") (pintype "passive"))
    )
    (net (code "130") (name "H{slash}L-SWAP") (class "Default")
      (node (ref "IC1") (pin "13") (pinfunction "I_13") (pintype "input"))
      (node (ref "IC6") (pin "10") (pinfunction "I1_10") (pintype "input"))
      (node (ref "X2") (pin "C25") (pinfunction "B_C25") (pintype "passive"))
    )
    (net (code "131") (name "IN") (class "Default")
      (node (ref "X2") (pin "C26") (pinfunction "B_C26") (pintype "passive"))
    )
    (net (code "132") (name "INT") (class "Default")
      (node (ref "X2") (pin "B29") (pinfunction "B_B29") (pintype "passive"))
    )
    (net (code "133") (name "INTA") (class "Default")
      (node (ref "X2") (pin "B30") (pinfunction "B_B30") (pintype "passive"))
    )
    (net (code "134") (name "I{slash}D-REG-DN") (class "Default")
      (node (ref "X2") (pin "C5") (pinfunction "B_C5") (pintype "passive"))
    )
    (net (code "135") (name "I{slash}D-REG-LD") (class "Default")
      (node (ref "X2") (pin "C3") (pinfunction "B_C3") (pintype "passive"))
    )
    (net (code "136") (name "I{slash}D-REG-RD") (class "Default")
      (node (ref "X2") (pin "C4") (pinfunction "B_C4") (pintype "passive"))
    )
    (net (code "137") (name "I{slash}D-REG-UP") (class "Default")
      (node (ref "X2") (pin "C6") (pinfunction "B_C6") (pintype "passive"))
    )
    (net (code "138") (name "I{slash}O-ADDR") (class "Default")
      (node (ref "X2") (pin "B28") (pinfunction "B_B28") (pintype "passive"))
    )
    (net (code "139") (name "I{slash}O-RD") (class "Default")
      (node (ref "X2") (pin "B27") (pinfunction "B_B27") (pintype "passive"))
    )
    (net (code "140") (name "I{slash}O-WR") (class "Default")
      (node (ref "X2") (pin "B26") (pinfunction "B_B26") (pintype "passive"))
    )
    (net (code "141") (name "MEM-RD") (class "Default")
      (node (ref "X2") (pin "B25") (pinfunction "B_B25") (pintype "passive"))
    )
    (net (code "142") (name "MEM-WR") (class "Default")
      (node (ref "X2") (pin "B24") (pinfunction "B_B24") (pintype "passive"))
    )
    (net (code "143") (name "Net-(IC1F-O)") (class "Default")
      (node (ref "IC1") (pin "12") (pinfunction "O_12") (pintype "output"))
      (node (ref "IC6") (pin "1") (pinfunction "I0_1") (pintype "input"))
    )
    (net (code "144") (name "Net-(IC2A-G1)") (class "Default")
      (node (ref "IC2") (pin "6") (pinfunction "G1_6") (pintype "input"))
      (node (ref "IC3") (pin "6") (pinfunction "G1_6") (pintype "input"))
      (node (ref "R2") (pin "1") (pinfunction "1_1") (pintype "passive"))
    )
    (net (code "145") (name "Net-(IC4A-O)") (class "Default")
      (node (ref "IC4") (pin "3") (pinfunction "O_3") (pintype "output"))
      (node (ref "IC4") (pin "4") (pinfunction "I0_4") (pintype "input"))
    )
    (net (code "146") (name "Net-(IC4B-O)") (class "Default")
      (node (ref "IC4") (pin "6") (pinfunction "O_6") (pintype "output"))
      (node (ref "JP1") (pin "1") (pinfunction "1_1") (pintype "passive"))
    )
    (net (code "147") (name "Net-(IC4C-O)") (class "Default")
      (node (ref "IC4") (pin "8") (pinfunction "O_8") (pintype "output"))
      (node (ref "JP1") (pin "3") (pinfunction "3_3") (pintype "passive"))
    )
    (net (code "148") (name "Net-(IC4D-I0)") (class "Default")
      (node (ref "IC4") (pin "12") (pinfunction "I0_12") (pintype "input"))
      (node (ref "IC6") (pin "11") (pinfunction "O_11") (pintype "output"))
    )
    (net (code "149") (name "Net-(IC4D-O)") (class "Default")
      (node (ref "IC4") (pin "11") (pinfunction "O_11") (pintype "output"))
      (node (ref "JP2") (pin "1") (pinfunction "1_1") (pintype "passive"))
    )
    (net (code "150") (name "Net-(IC5A-O)") (class "Default")
      (node (ref "IC5") (pin "3") (pinfunction "O_3") (pintype "output"))
      (node (ref "IC5") (pin "5") (pinfunction "I1_5") (pintype "input"))
      (node (ref "IC6") (pin "2") (pinfunction "I1_2") (pintype "input"))
      (node (ref "IC6") (pin "9") (pinfunction "I0_9") (pintype "input"))
    )
    (net (code "151") (name "Net-(IC5B-O)") (class "Default")
      (node (ref "IC5") (pin "6") (pinfunction "O_6") (pintype "output"))
      (node (ref "IC8") (pin "19") (pinfunction "G_19") (pintype "input"))
    )
    (net (code "152") (name "Net-(IC6A-O)") (class "Default")
      (node (ref "IC6") (pin "3") (pinfunction "O_3") (pintype "output"))
      (node (ref "IC7") (pin "19") (pinfunction "G_19") (pintype "input"))
    )
    (net (code "153") (name "Net-(IC6B-O)") (class "Default")
      (node (ref "IC6") (pin "6") (pinfunction "O_6") (pintype "output"))
      (node (ref "JP2") (pin "3") (pinfunction "3_3") (pintype "passive"))
    )
    (net (code "154") (name "Net-(IC6C-O)") (class "Default")
      (node (ref "IC6") (pin "8") (pinfunction "O_8") (pintype "output"))
      (node (ref "IC9") (pin "19") (pinfunction "G_19") (pintype "input"))
    )
    (net (code "155") (name "Net-(IC10A-OC)") (class "Default")
      (node (ref "IC10") (pin "1") (pinfunction "OC_1") (pintype "input"))
      (node (ref "IC32") (pin "3") (pinfunction "O_3") (pintype "output"))
    )
    (net (code "156") (name "Net-(IC11A-G)") (class "Default")
      (node (ref "IC11") (pin "1") (pinfunction "G_1") (pintype "input"))
      (node (ref "IC11") (pin "19") (pinfunction "G_19") (pintype "input"))
      (node (ref "IC12") (pin "1") (pinfunction "G_1") (pintype "input"))
      (node (ref "IC12") (pin "19") (pinfunction "G_19") (pintype "input"))
      (node (ref "IC33") (pin "1") (pinfunction "G_1") (pintype "input"))
      (node (ref "IC33") (pin "19") (pinfunction "G_19") (pintype "input"))
      (node (ref "IC34") (pin "1") (pinfunction "G_1") (pintype "input"))
      (node (ref "IC34") (pin "19") (pinfunction "G_19") (pintype "input"))
      (node (ref "J1") (pin "1") (pinfunction "1_1") (pintype "passive"))
      (node (ref "R1") (pin "1") (pinfunction "1_1") (pintype "passive"))
    )
    (net (code "157") (name "Net-(IC13A-O)") (class "Default")
      (node (ref "IC13") (pin "3") (pinfunction "O_3") (pintype "output"))
      (node (ref "IC15") (pin "1") (pinfunction "OC_1") (pintype "input"))
    )
    (net (code "158") (name "Net-(IC13B-O)") (class "Default")
      (node (ref "IC13") (pin "6") (pinfunction "O_6") (pintype "output"))
      (node (ref "IC16") (pin "1") (pinfunction "OC_1") (pintype "input"))
    )
    (net (code "159") (name "Net-(IC13C-O)") (class "Default")
      (node (ref "IC13") (pin "8") (pinfunction "O_8") (pintype "output"))
      (node (ref "IC17") (pin "1") (pinfunction "OC_1") (pintype "input"))
    )
    (net (code "160") (name "Net-(IC13D-O)") (class "Default")
      (node (ref "IC13") (pin "11") (pinfunction "O_11") (pintype "output"))
      (node (ref "IC18") (pin "1") (pinfunction "OC_1") (pintype "input"))
    )
    (net (code "161") (name "Net-(IC19A-O)") (class "Default")
      (node (ref "IC19") (pin "3") (pinfunction "O_3") (pintype "output"))
      (node (ref "IC21") (pin "1") (pinfunction "OC_1") (pintype "input"))
    )
    (net (code "162") (name "Net-(IC19B-O)") (class "Default")
      (node (ref "IC19") (pin "6") (pinfunction "O_6") (pintype "output"))
      (node (ref "IC22") (pin "1") (pinfunction "OC_1") (pintype "input"))
    )
    (net (code "163") (name "Net-(IC19C-O)") (class "Default")
      (node (ref "IC19") (pin "8") (pinfunction "O_8") (pintype "output"))
      (node (ref "IC23") (pin "1") (pinfunction "OC_1") (pintype "input"))
    )
    (net (code "164") (name "Net-(IC19D-O)") (class "Default")
      (node (ref "IC19") (pin "11") (pinfunction "O_11") (pintype "output"))
      (node (ref "IC24") (pin "1") (pinfunction "OC_1") (pintype "input"))
    )
    (net (code "165") (name "Net-(IC25A-OC)") (class "Default")
      (node (ref "IC25") (pin "1") (pinfunction "OC_1") (pintype "input"))
      (node (ref "IC32") (pin "6") (pinfunction "O_6") (pintype "output"))
    )
    (net (code "166") (name "Net-(IC26A-OC)") (class "Default")
      (node (ref "IC26") (pin "1") (pinfunction "OC_1") (pintype "input"))
      (node (ref "IC37") (pin "3") (pinfunction "O_3") (pintype "output"))
    )
    (net (code "167") (name "Net-(IC27A-OC)") (class "Default")
      (node (ref "IC27") (pin "1") (pinfunction "OC_1") (pintype "input"))
      (node (ref "IC37") (pin "6") (pinfunction "O_6") (pintype "output"))
    )
    (net (code "168") (name "Net-(IC28A-OC)") (class "Default")
      (node (ref "IC28") (pin "1") (pinfunction "OC_1") (pintype "input"))
      (node (ref "IC32") (pin "8") (pinfunction "O_8") (pintype "output"))
    )
    (net (code "169") (name "Net-(IC29A-OC)") (class "Default")
      (node (ref "IC29") (pin "1") (pinfunction "OC_1") (pintype "input"))
      (node (ref "IC32") (pin "11") (pinfunction "O_11") (pintype "output"))
    )
    (net (code "170") (name "Net-(IC30A-OC)") (class "Default")
      (node (ref "IC30") (pin "1") (pinfunction "OC_1") (pintype "input"))
      (node (ref "IC37") (pin "8") (pinfunction "O_8") (pintype "output"))
    )
    (net (code "171") (name "Net-(IC31A-OC)") (class "Default")
      (node (ref "IC31") (pin "1") (pinfunction "OC_1") (pintype "input"))
      (node (ref "IC37") (pin "11") (pinfunction "O_11") (pintype "output"))
    )
    (net (code "172") (name "Net-(PWR-PadA)") (class "Default")
      (node (ref "PWR") (pin "A") (pinfunction "A_A") (pintype "passive"))
      (node (ref "R3") (pin "1") (pinfunction "1_1") (pintype "passive"))
    )
    (net (code "173") (name "OUT") (class "Default")
      (node (ref "X2") (pin "C27") (pinfunction "B_C27") (pintype "passive"))
    )
    (net (code "174") (name "REG-BRD-LD-ID") (class "Default")
      (node (ref "IC6") (pin "12") (pinfunction "I0_12") (pintype "input"))
      (node (ref "IC6") (pin "13") (pinfunction "I1_13") (pintype "input"))
      (node (ref "IC6") (pin "5") (pinfunction "I1_5") (pintype "input"))
      (node (ref "X2") (pin "B16") (pinfunction "B_B16") (pintype "passive"))
    )
    (net (code "175") (name "REG-BRD-RD-ID") (class "Default")
      (node (ref "IC4") (pin "1") (pinfunction "I0_1") (pintype "input"))
      (node (ref "IC4") (pin "10") (pinfunction "I1_10") (pintype "input"))
      (node (ref "IC4") (pin "2") (pinfunction "I1_2") (pintype "input"))
      (node (ref "X2") (pin "B12") (pinfunction "B_B12") (pintype "passive"))
    )
    (net (code "176") (name "REG-FUNC") (class "Default")
      (node (ref "IC4") (pin "13") (pinfunction "I1_13") (pintype "input"))
      (node (ref "IC4") (pin "5") (pinfunction "I1_5") (pintype "input"))
      (node (ref "IC4") (pin "9") (pinfunction "I0_9") (pintype "input"))
      (node (ref "IC6") (pin "4") (pinfunction "I0_4") (pintype "input"))
      (node (ref "X2") (pin "B7") (pinfunction "B_B7") (pintype "passive"))
    )
    (net (code "177") (name "REG-LD-HI") (class "Default")
      (node (ref "IC1") (pin "9") (pinfunction "I_9") (pintype "input"))
      (node (ref "X2") (pin "B23") (pinfunction "B_B23") (pintype "passive"))
    )
    (net (code "178") (name "REG-LD-ID0") (class "Default")
      (node (ref "IC3") (pin "1") (pinfunction "A_1") (pintype "input"))
      (node (ref "X2") (pin "B17") (pinfunction "B_B17") (pintype "passive"))
    )
    (net (code "179") (name "REG-LD-ID1") (class "Default")
      (node (ref "IC3") (pin "2") (pinfunction "B_2") (pintype "input"))
      (node (ref "X2") (pin "B18") (pinfunction "B_B18") (pintype "passive"))
    )
    (net (code "180") (name "REG-LD-ID2") (class "Default")
      (node (ref "IC3") (pin "3") (pinfunction "C_3") (pintype "input"))
      (node (ref "X2") (pin "B19") (pinfunction "B_B19") (pintype "passive"))
    )
    (net (code "181") (name "REG-LD-LO") (class "Default")
      (node (ref "IC1") (pin "3") (pinfunction "I_3") (pintype "input"))
      (node (ref "X2") (pin "B21") (pinfunction "B_B21") (pintype "passive"))
    )
    (net (code "182") (name "REG-RD-HI") (class "Default")
      (node (ref "IC1") (pin "5") (pinfunction "I_5") (pintype "input"))
      (node (ref "X2") (pin "B22") (pinfunction "B_B22") (pintype "passive"))
    )
    (net (code "183") (name "REG-RD-ID0") (class "Default")
      (node (ref "IC2") (pin "1") (pinfunction "A_1") (pintype "input"))
      (node (ref "X2") (pin "B13") (pinfunction "B_B13") (pintype "passive"))
    )
    (net (code "184") (name "REG-RD-ID1") (class "Default")
      (node (ref "IC2") (pin "2") (pinfunction "B_2") (pintype "input"))
      (node (ref "X2") (pin "B14") (pinfunction "B_B14") (pintype "passive"))
    )
    (net (code "185") (name "REG-RD-ID2") (class "Default")
      (node (ref "IC2") (pin "3") (pinfunction "C_3") (pintype "input"))
      (node (ref "X2") (pin "B15") (pinfunction "B_B15") (pintype "passive"))
    )
    (net (code "186") (name "REG-RD-LO") (class "Default")
      (node (ref "IC1") (pin "1") (pinfunction "I_1") (pintype "input"))
      (node (ref "X2") (pin "B20") (pinfunction "B_B20") (pintype "passive"))
    )
    (net (code "187") (name "RESET") (class "Default")
      (node (ref "X2") (pin "C30") (pinfunction "B_C30") (pintype "passive"))
    )
    (net (code "188") (name "RUN") (class "Default")
      (node (ref "X2") (pin "C29") (pinfunction "B_C29") (pintype "passive"))
    )
    (net (code "189") (name "SP{slash}PC-ADDR-RD") (class "Default")
      (node (ref "X2") (pin "C10") (pinfunction "B_C10") (pintype "passive"))
    )
    (net (code "190") (name "SP{slash}PC-DATA-RD-HI") (class "Default")
      (node (ref "X2") (pin "C9") (pinfunction "B_C9") (pintype "passive"))
    )
    (net (code "191") (name "SP{slash}PC-DATA-RD-LO") (class "Default")
      (node (ref "X2") (pin "C8") (pinfunction "B_C8") (pintype "passive"))
    )
    (net (code "192") (name "SP{slash}PC-DN") (class "Default")
      (node (ref "X2") (pin "C13") (pinfunction "B_C13") (pintype "passive"))
    )
    (net (code "193") (name "SP{slash}PC-LD-HI") (class "Default")
      (node (ref "X2") (pin "C12") (pinfunction "B_C12") (pintype "passive"))
    )
    (net (code "194") (name "SP{slash}PC-LD-LO") (class "Default")
      (node (ref "X2") (pin "C11") (pinfunction "B_C11") (pintype "passive"))
    )
    (net (code "195") (name "SP{slash}PC-SEL") (class "Default")
      (node (ref "X2") (pin "C7") (pinfunction "B_C7") (pintype "passive"))
    )
    (net (code "196") (name "SP{slash}PC-UP") (class "Default")
      (node (ref "X2") (pin "C14") (pinfunction "B_C14") (pintype "passive"))
    )
    (net (code "197") (name "SR-LD") (class "Default")
      (node (ref "X2") (pin "C23") (pinfunction "B_C23") (pintype "passive"))
    )
    (net (code "198") (name "UNUSED1") (class "Default")
      (node (ref "X2") (pin "C28") (pinfunction "B_C28") (pintype "passive"))
    )
    (net (code "199") (name "UNUSED2") (class "Default")
      (node (ref "X2") (pin "B8") (pinfunction "B_B8") (pintype "passive"))
    )
    (net (code "200") (name "UNUSED3") (class "Default")
      (node (ref "X2") (pin "B9") (pinfunction "B_B9") (pintype "passive"))
    )
    (net (code "201") (name "UNUSED4") (class "Default")
      (node (ref "X2") (pin "B10") (pinfunction "B_B10") (pintype "passive"))
    )
    (net (code "202") (name "UNUSED5") (class "Default")
      (node (ref "X2") (pin "B11") (pinfunction "B_B11") (pintype "passive"))
    )
    (net (code "203") (name "VCC") (class "Default")
      (node (ref "C1") (pin "1") (pinfunction "1_1") (pintype "passive"))
      (node (ref "C10") (pin "1") (pinfunction "1_1") (pintype "passive"))
      (node (ref "C11") (pin "1") (pinfunction "1_1") (pintype "passive"))
      (node (ref "C12") (pin "1") (pinfunction "1_1") (pintype "passive"))
      (node (ref "C13") (pin "1") (pinfunction "1_1") (pintype "passive"))
      (node (ref "C14") (pin "1") (pinfunction "1_1") (pintype "passive"))
      (node (ref "C15") (pin "1") (pinfunction "1_1") (pintype "passive"))
      (node (ref "C16") (pin "1") (pinfunction "1_1") (pintype "passive"))
      (node (ref "C17") (pin "1") (pinfunction "1_1") (pintype "passive"))
      (node (ref "C18") (pin "1") (pinfunction "1_1") (pintype "passive"))
      (node (ref "C19") (pin "1") (pinfunction "1_1") (pintype "passive"))
      (node (ref "C2") (pin "1") (pinfunction "1_1") (pintype "passive"))
      (node (ref "C20") (pin "1") (pinfunction "1_1") (pintype "passive"))
      (node (ref "C21") (pin "1") (pinfunction "1_1") (pintype "passive"))
      (node (ref "C22") (pin "1") (pinfunction "1_1") (pintype "passive"))
      (node (ref "C23") (pin "1") (pinfunction "1_1") (pintype "passive"))
      (node (ref "C24") (pin "1") (pinfunction "1_1") (pintype "passive"))
      (node (ref "C25") (pin "1") (pinfunction "1_1") (pintype "passive"))
      (node (ref "C26") (pin "1") (pinfunction "1_1") (pintype "passive"))
      (node (ref "C27") (pin "1") (pinfunction "1_1") (pintype "passive"))
      (node (ref "C28") (pin "1") (pinfunction "1_1") (pintype "passive"))
      (node (ref "C29") (pin "1") (pinfunction "1_1") (pintype "passive"))
      (node (ref "C3") (pin "1") (pinfunction "1_1") (pintype "passive"))
      (node (ref "C30") (pin "1") (pinfunction "1_1") (pintype "passive"))
      (node (ref "C31") (pin "1") (pinfunction "1_1") (pintype "passive"))
      (node (ref "C32") (pin "1") (pinfunction "1_1") (pintype "passive"))
      (node (ref "C33") (pin "1") (pinfunction "1_1") (pintype "passive"))
      (node (ref "C34") (pin "1") (pinfunction "1_1") (pintype "passive"))
      (node (ref "C35") (pin "1") (pinfunction "1_1") (pintype "passive"))
      (node (ref "C36") (pin "1") (pinfunction "1_1") (pintype "passive"))
      (node (ref "C37") (pin "1") (pinfunction "1_1") (pintype "passive"))
      (node (ref "C4") (pin "1") (pinfunction "1_1") (pintype "passive"))
      (node (ref "C5") (pin "1") (pinfunction "1_1") (pintype "passive"))
      (node (ref "C6") (pin "1") (pinfunction "1_1") (pintype "passive"))
      (node (ref "C7") (pin "1") (pinfunction "1_1") (pintype "passive"))
      (node (ref "C8") (pin "1") (pinfunction "1_1") (pintype "passive"))
      (node (ref "C9") (pin "1") (pinfunction "1_1") (pintype "passive"))
      (node (ref "IC5") (pin "4") (pinfunction "I0_4") (pintype "input"))
      (node (ref "JP6") (pin "1") (pinfunction "1_1") (pintype "passive"))
      (node (ref "JP6") (pin "2") (pinfunction "2_2") (pintype "passive"))
      (node (ref "R1") (pin "2") (pinfunction "2_2") (pintype "passive"))
      (node (ref "R2") (pin "2") (pinfunction "2_2") (pintype "passive"))
      (node (ref "R3") (pin "2") (pinfunction "2_2") (pintype "passive"))
      (node (ref "RN1") (pin "1") (pinfunction "1_1") (pintype "passive"))
      (node (ref "RN2") (pin "1") (pinfunction "1_1") (pintype "passive"))
      (node (ref "X2") (pin "A2") (pinfunction "B_A2") (pintype "passive"))
      (node (ref "X2") (pin "A31") (pinfunction "B_A31") (pintype "passive"))
      (node (ref "X2") (pin "B2") (pinfunction "B_B2") (pintype "passive"))
      (node (ref "X2") (pin "B31") (pinfunction "B_B31") (pintype "passive"))
      (node (ref "X2") (pin "C2") (pinfunction "B_C2") (pintype "passive"))
      (node (ref "X2") (pin "C31") (pinfunction "B_C31") (pintype "passive"))
    )
    (net (code "204") (name "unconnected-(IC5C-O-Pad8)") (class "Default")
      (node (ref "IC5") (pin "8") (pinfunction "O_8") (pintype "output"))
    )
    (net (code "205") (name "unconnected-(IC5D-O-Pad11)") (class "Default")
      (node (ref "IC5") (pin "11") (pinfunction "O_11") (pintype "output"))
    )
    (net (code "206") (name "unconnected-(JP6-Pad35)") (class "Default")
      (node (ref "JP6") (pin "35") (pinfunction "35_35") (pintype "passive"))
    )
    (net (code "207") (name "unconnected-(JP6-Pad36)") (class "Default")
      (node (ref "JP6") (pin "36") (pinfunction "36_36") (pintype "passive"))
    )
    (net (code "208") (name "unconnected-(JP6-Pad37)") (class "Default")
      (node (ref "JP6") (pin "37") (pinfunction "37_37") (pintype "passive"))
    )
    (net (code "209") (name "unconnected-(JP6-Pad38)") (class "Default")
      (node (ref "JP6") (pin "38") (pinfunction "38_38") (pintype "passive"))
    )
  )
)
